# Schematic_V1.net
KiCad netlist of a schematic drawn in EAGLE
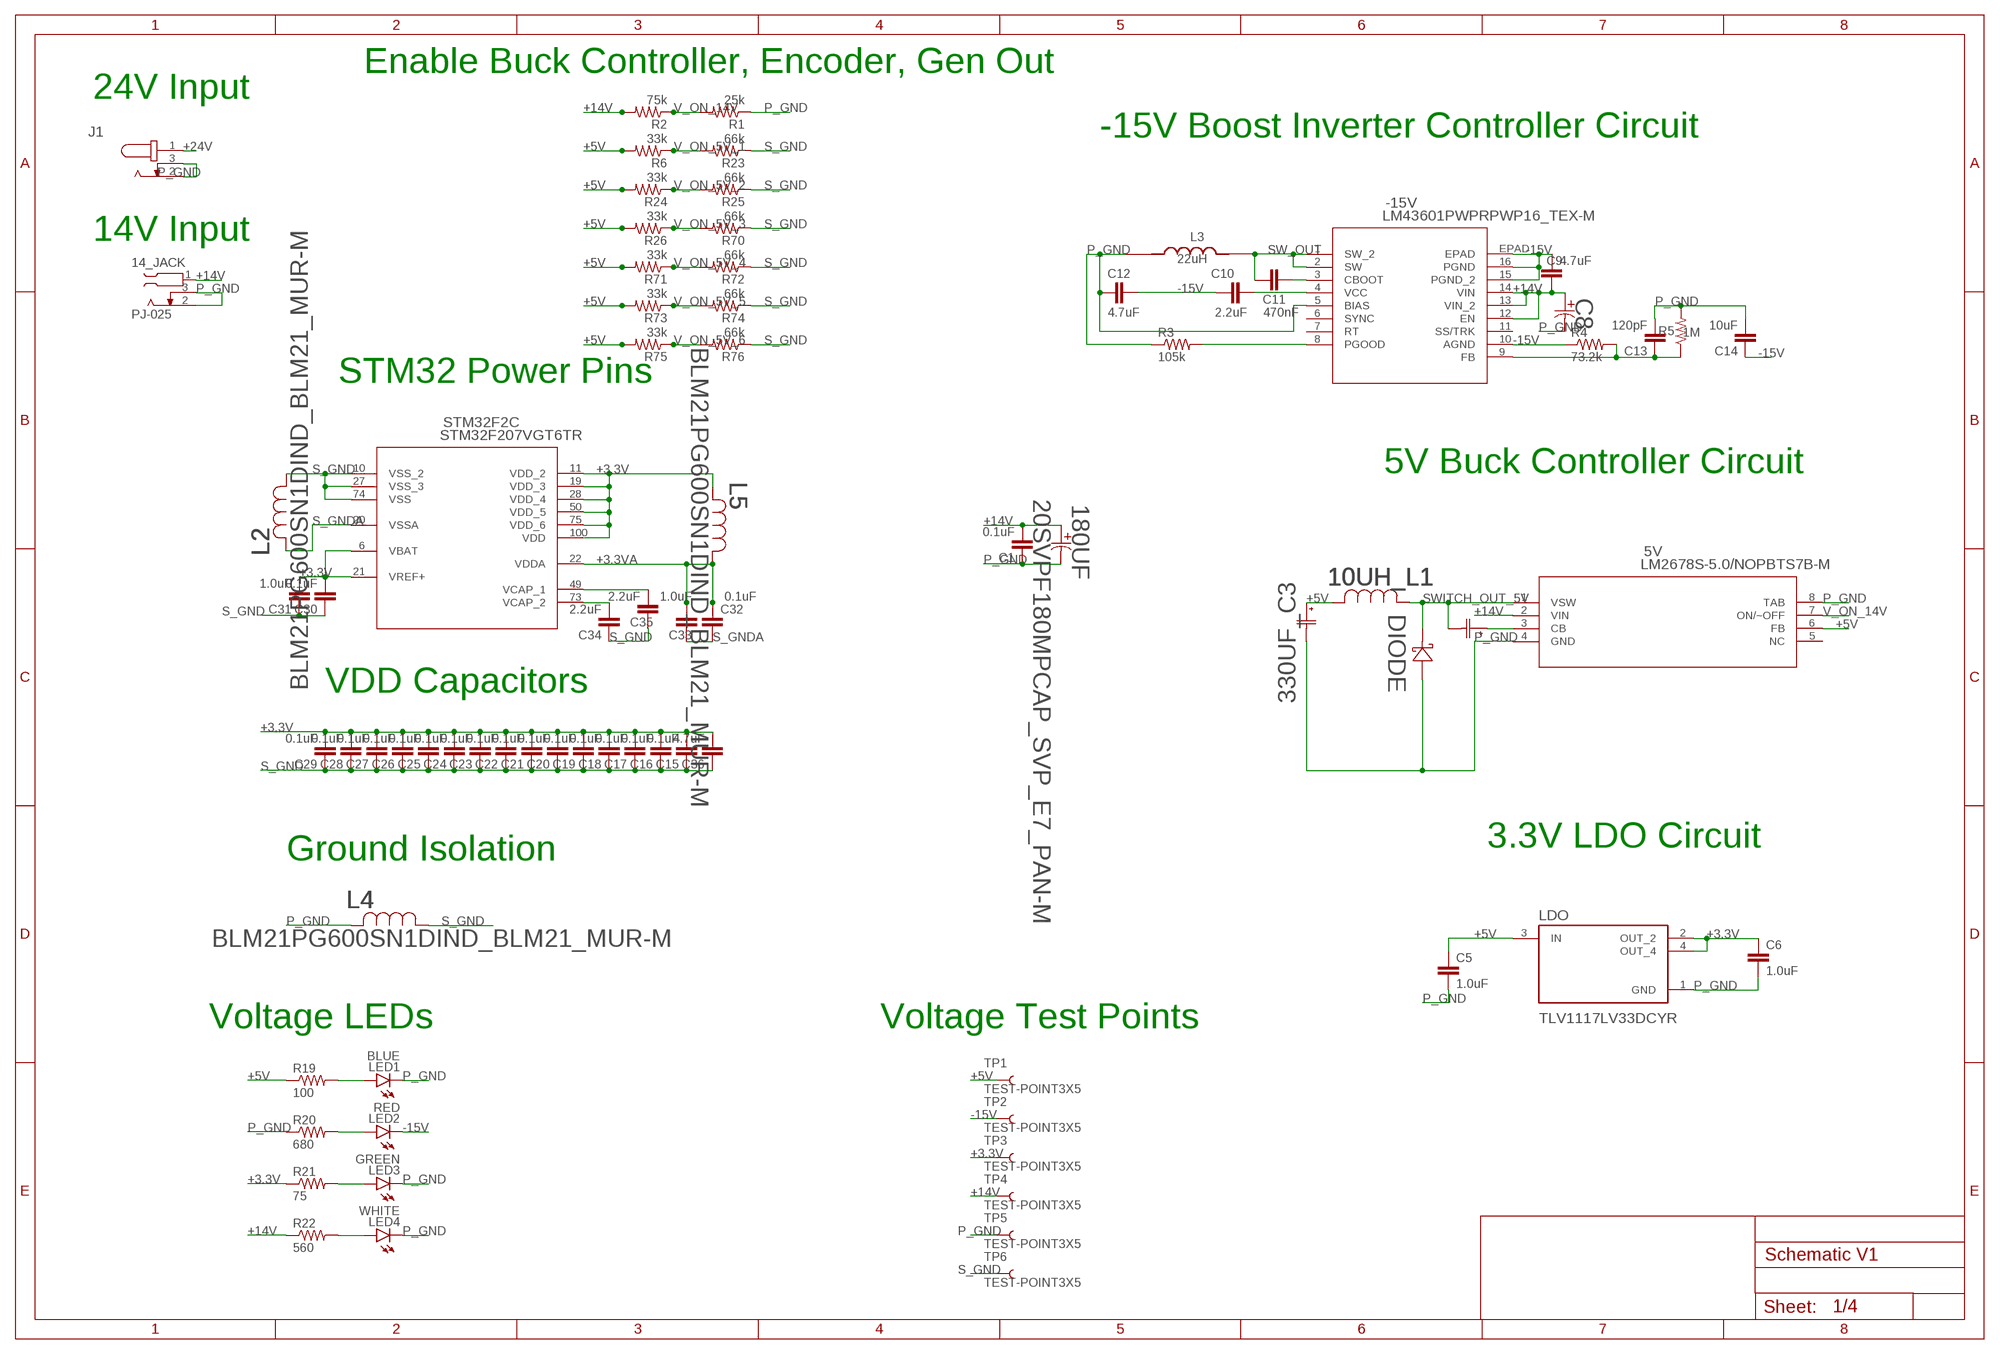
[diagram p0: schematic, sheet 1]
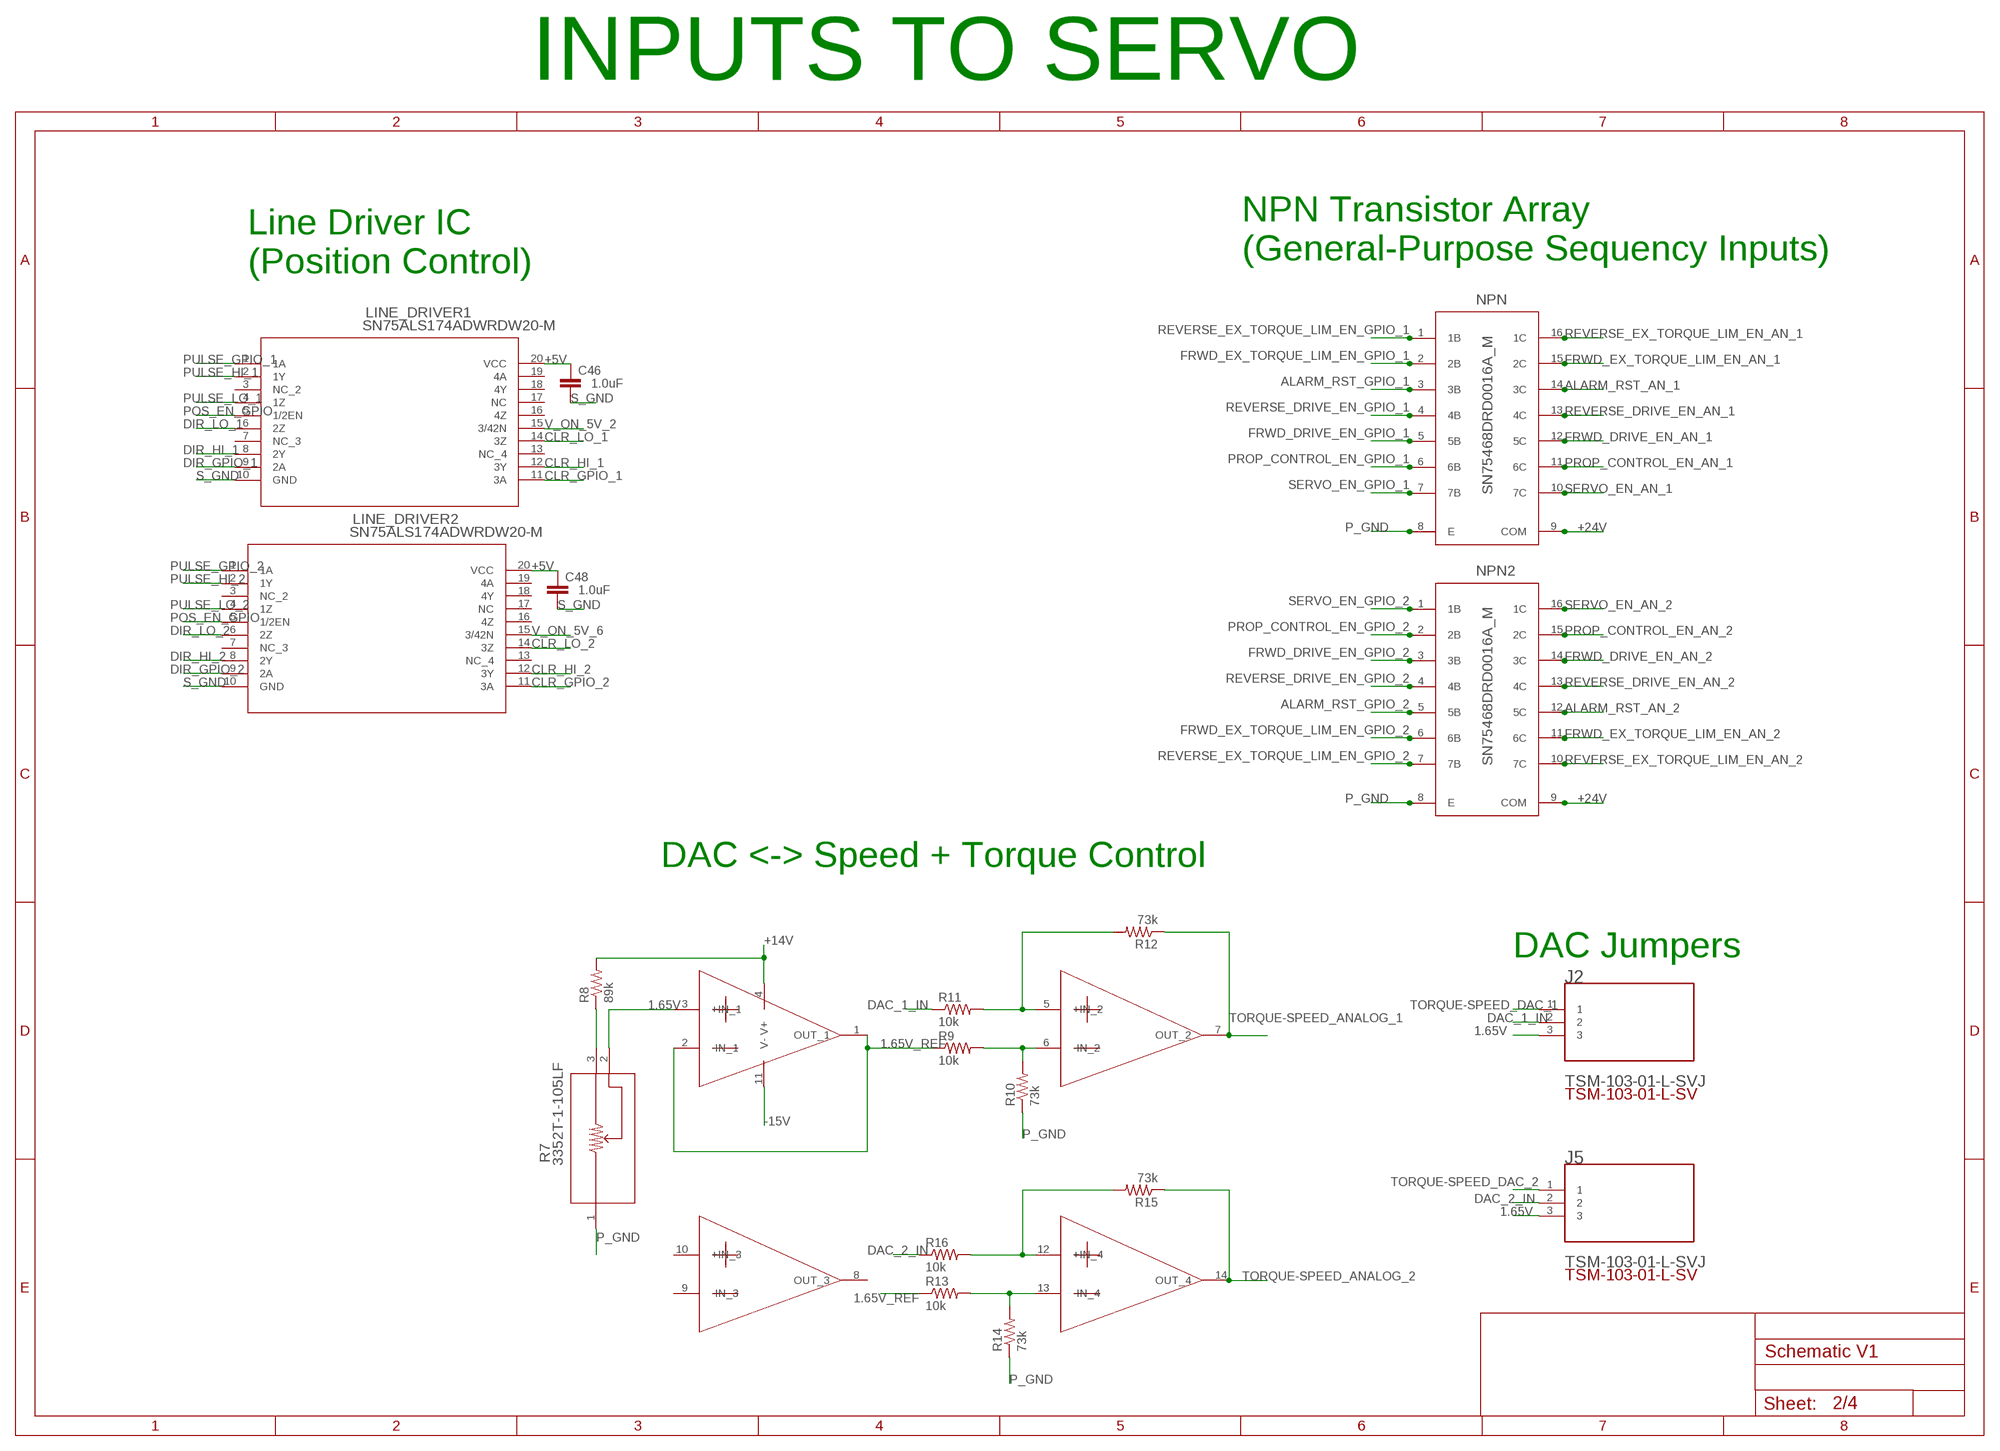
[diagram p1: schematic, sheet 2]
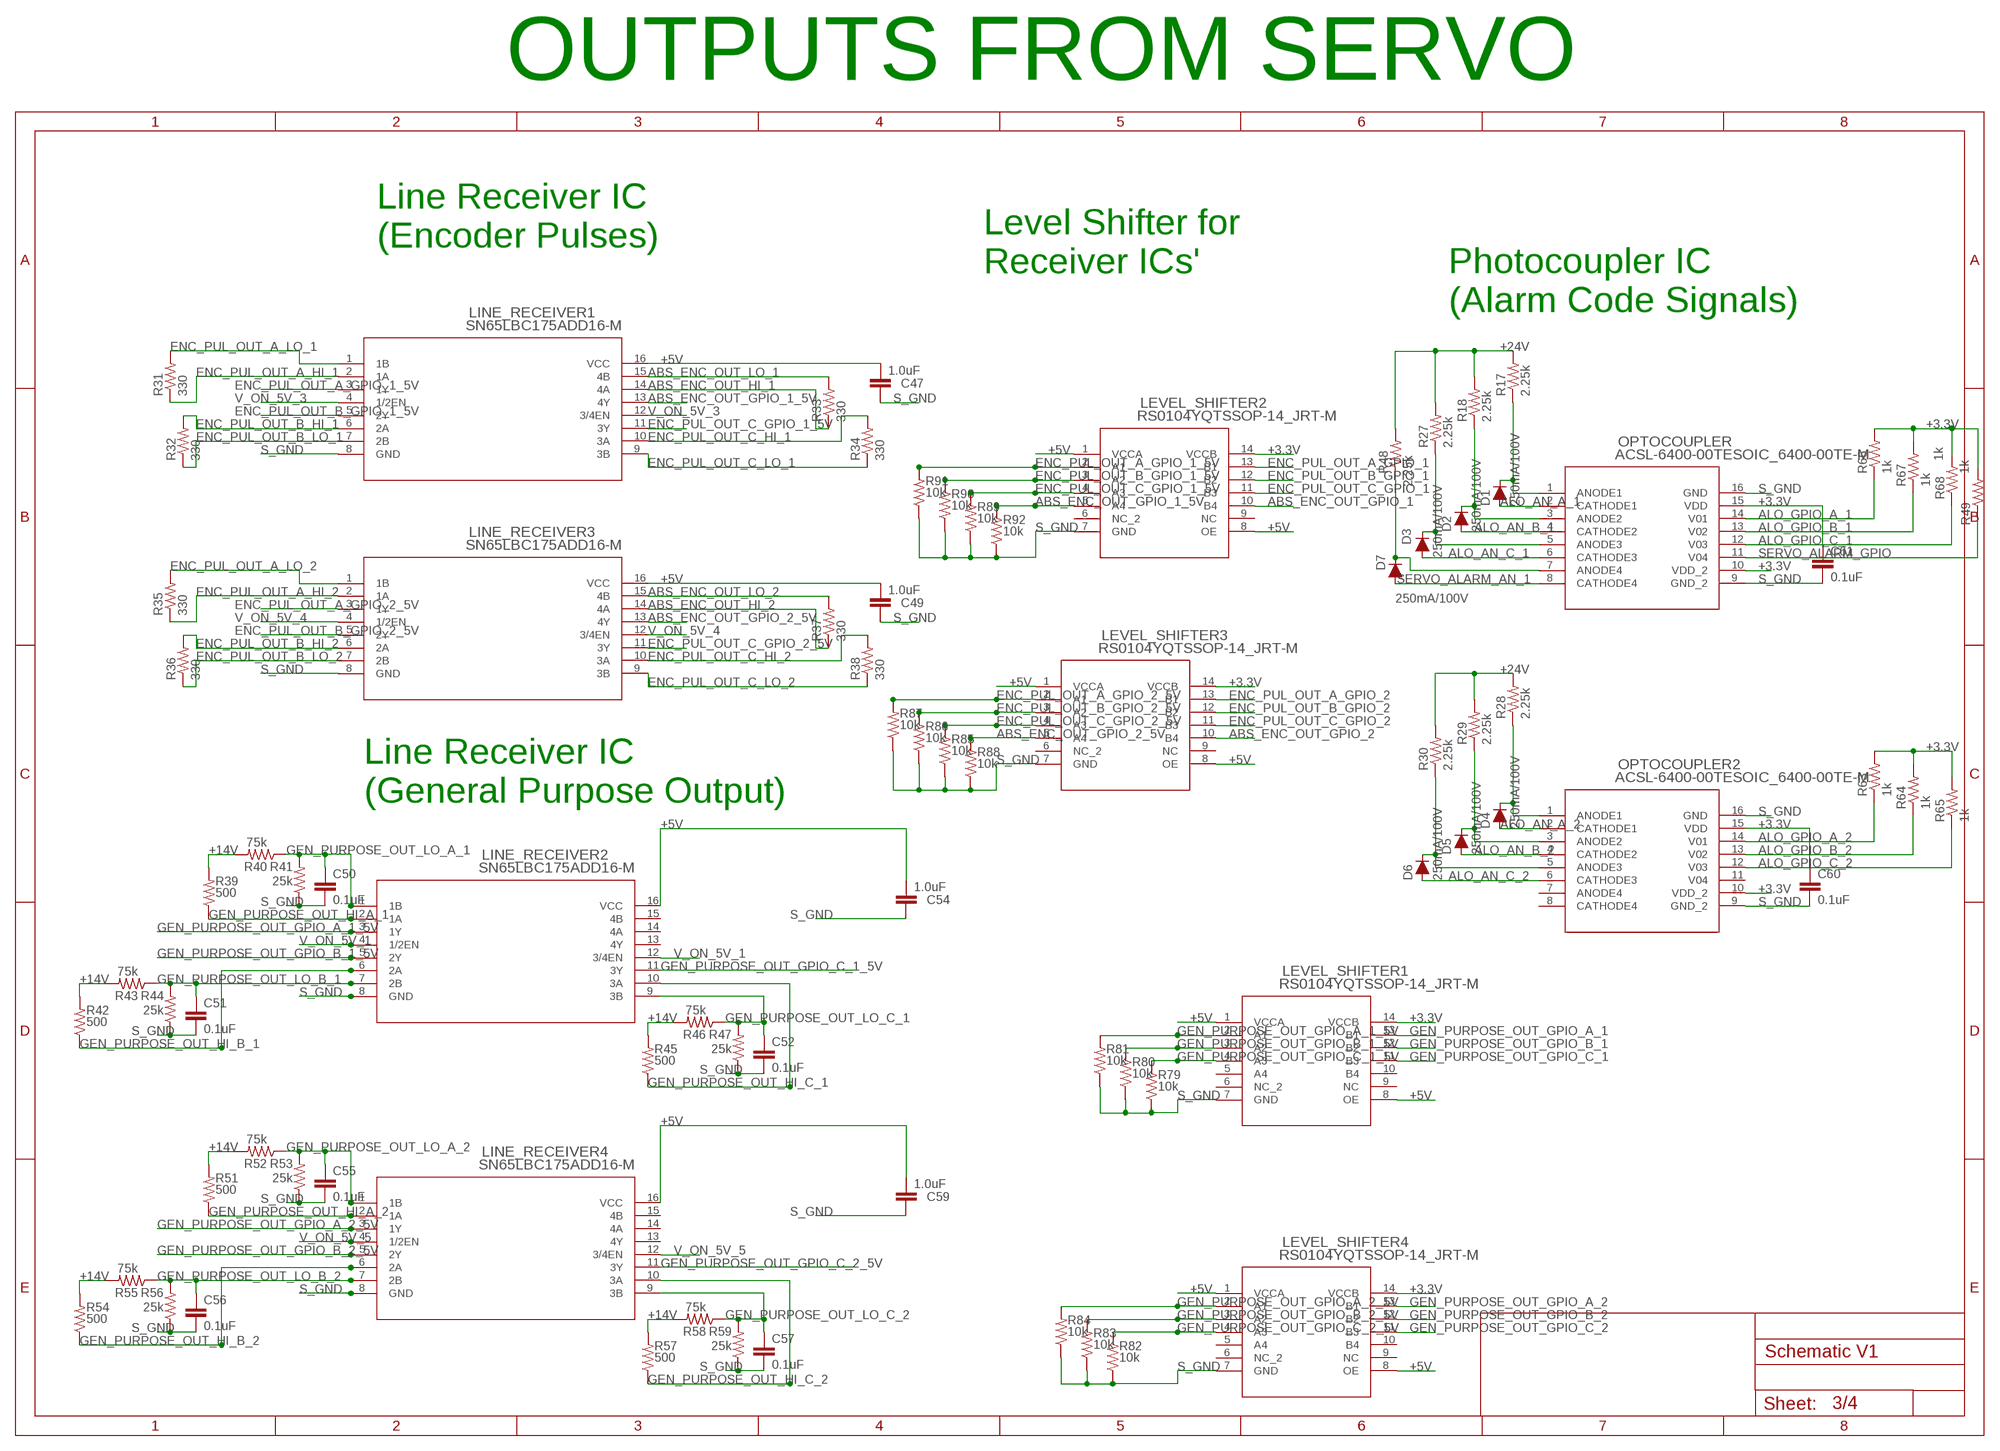
[diagram p2: schematic, sheet 3]
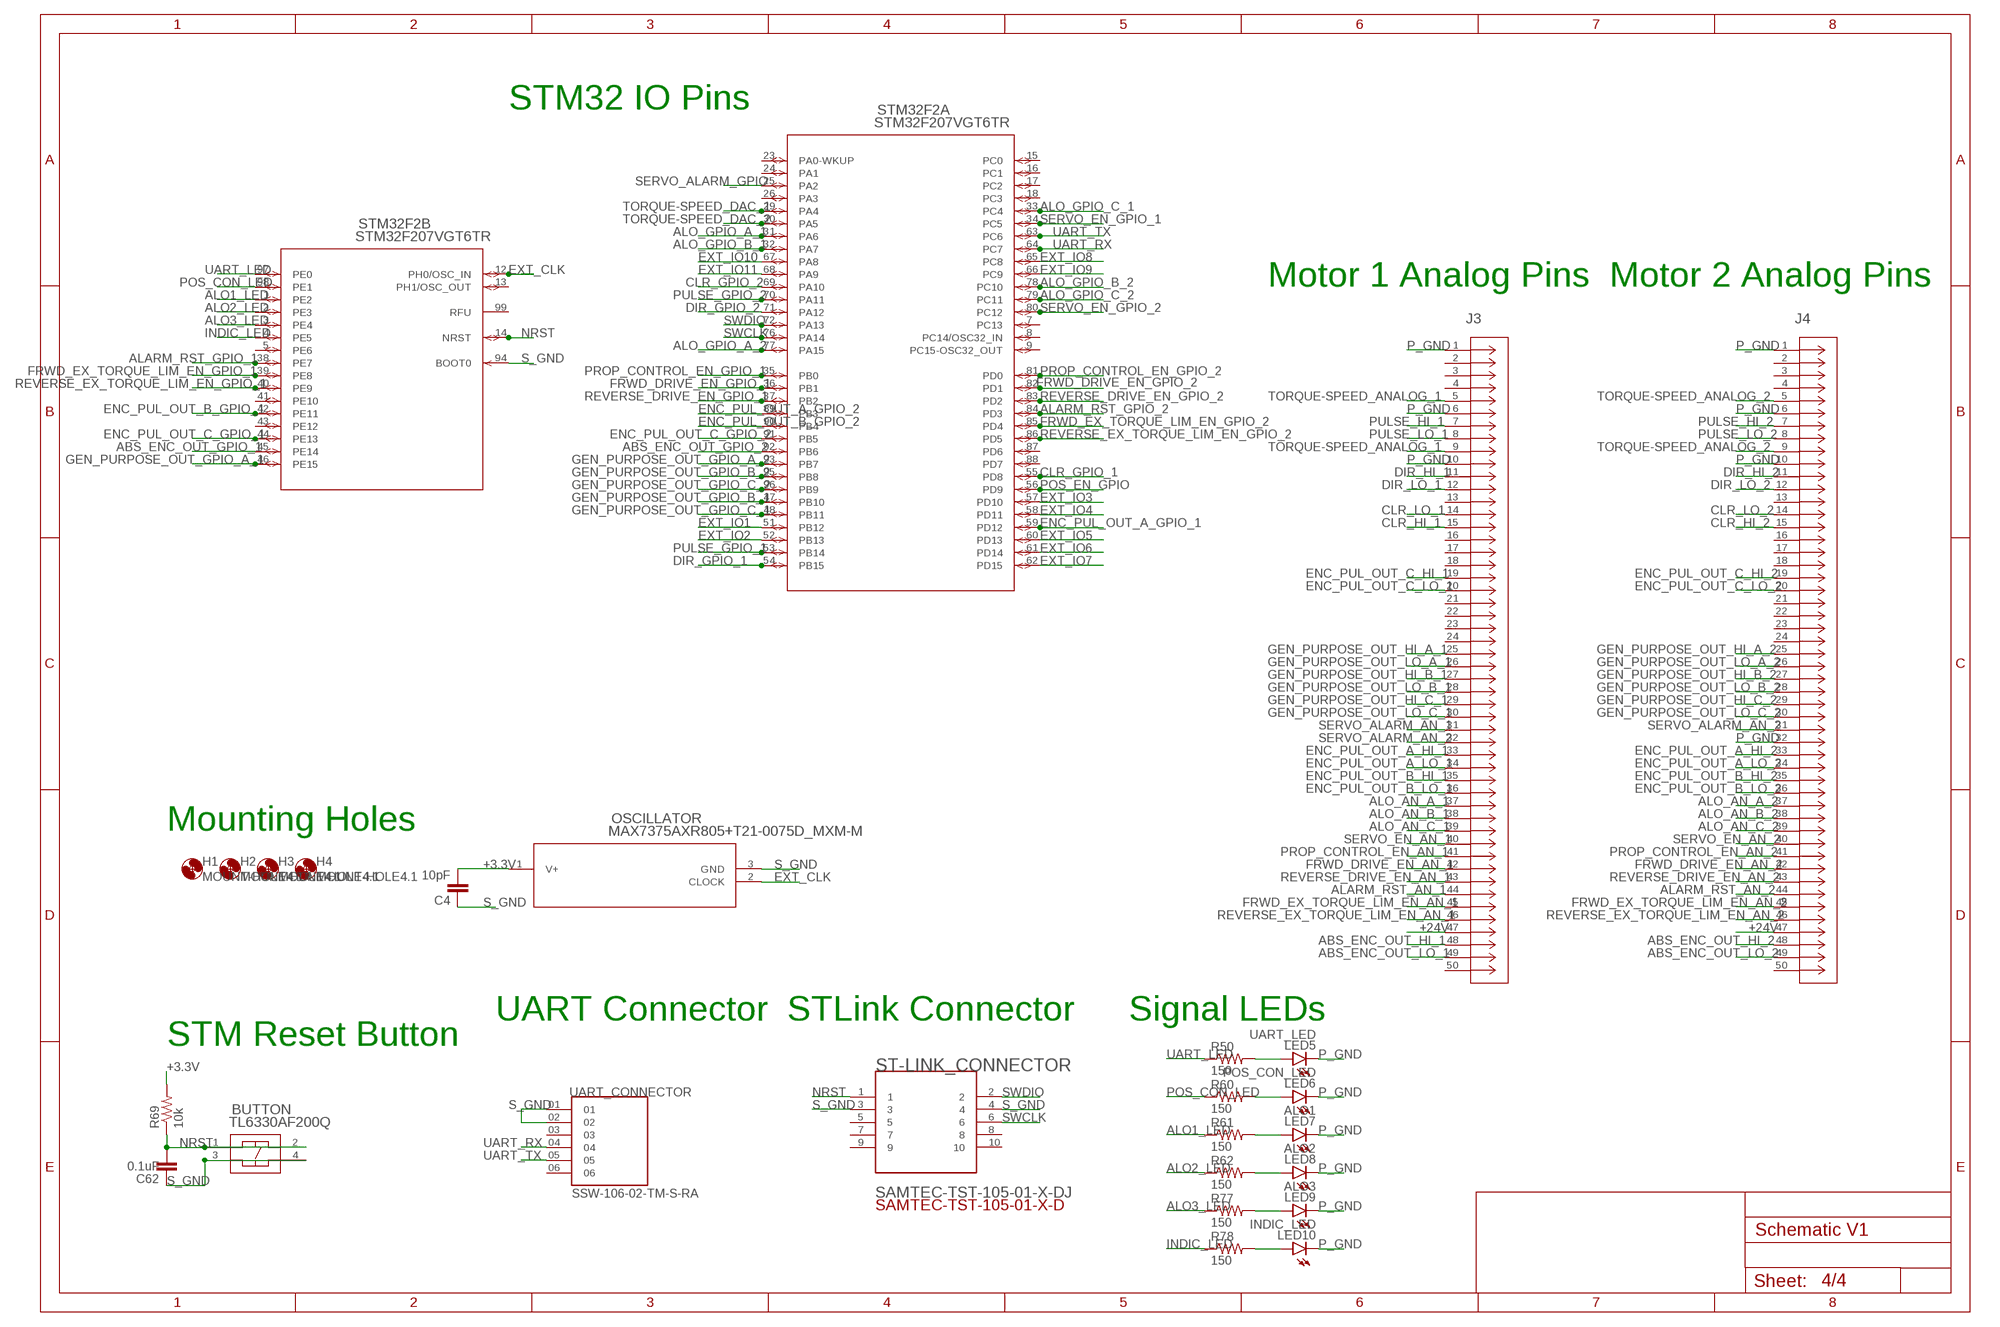
[diagram p3: schematic, sheet 4]

(export (version "E")
  (design (tool "Eeschema 10.0.6"))
  (components
    (comp (ref "BUTTON")
      (value "TL6330AF200Q")
      (footprint "eagle-import:TL6330_EWI")
      (fields (field (name "COPYRIGHT") "Copyright (C) 2024 Ultra Librarian. All rights reserved."))
      (libsource (lib "eagle-import") (part "TL6330AF200Q"))
    )
    (comp (ref "C4")
      (value "10pF")
      (footprint "eagle-import:0805")
      (libsource (lib "eagle-import") (part "10UF-0805-25V-10%"))
    )
    (comp (ref "C62")
      (value "0.1uF")
      (footprint "eagle-import:0805")
      (libsource (lib "eagle-import") (part "1.0UF-0805-25V-10%"))
    )
    (comp (ref "H1")
      (value "MOUNT-HOLE4.1")
      (footprint "eagle-import:4,1")
      (libsource (lib "eagle-import") (part "MOUNT-HOLE4.1"))
    )
    (comp (ref "H2")
      (value "MOUNT-HOLE4.1")
      (footprint "eagle-import:4,1")
      (libsource (lib "eagle-import") (part "MOUNT-HOLE4.1"))
    )
    (comp (ref "H3")
      (value "MOUNT-HOLE4.1")
      (footprint "eagle-import:4,1")
      (libsource (lib "eagle-import") (part "MOUNT-HOLE4.1"))
    )
    (comp (ref "H4")
      (value "MOUNT-HOLE4.1")
      (footprint "eagle-import:4,1")
      (libsource (lib "eagle-import") (part "MOUNT-HOLE4.1"))
    )
    (comp (ref "J3")
      (value "DD50P564GTXLF")
      (footprint "eagle-import:CONN_DD50P564GTXLF_AMP")
      (fields (field (name "COPYRIGHT") "Copyright (C) 2024 Ultra Librarian. All rights reserved."))
      (libsource (lib "eagle-import") (part "DD50P564GTXLF"))
    )
    (comp (ref "J4")
      (value "DD50P564GTXLF")
      (footprint "eagle-import:CONN_DD50P564GTXLF_AMP")
      (fields (field (name "COPYRIGHT") "Copyright (C) 2024 Ultra Librarian. All rights reserved."))
      (libsource (lib "eagle-import") (part "DD50P564GTXLF"))
    )
    (comp (ref "LED5")
      (value "UART_LED")
      (footprint "eagle-import:CHIPLED_0805")
      (libsource (lib "eagle-import") (part "LEDCHIPLED_0805"))
    )
    (comp (ref "LED6")
      (value "POS_CON_LED")
      (footprint "eagle-import:CHIPLED_0805")
      (libsource (lib "eagle-import") (part "LEDCHIPLED_0805"))
    )
    (comp (ref "LED7")
      (value "ALO1")
      (footprint "eagle-import:CHIPLED_0805")
      (libsource (lib "eagle-import") (part "LEDCHIPLED_0805"))
    )
    (comp (ref "LED8")
      (value "ALO2")
      (footprint "eagle-import:CHIPLED_0805")
      (libsource (lib "eagle-import") (part "LEDCHIPLED_0805"))
    )
    (comp (ref "LED9")
      (value "ALO3")
      (footprint "eagle-import:CHIPLED_0805")
      (libsource (lib "eagle-import") (part "LEDCHIPLED_0805"))
    )
    (comp (ref "LED10")
      (value "INDIC_LED")
      (footprint "eagle-import:CHIPLED_0805")
      (libsource (lib "eagle-import") (part "LEDCHIPLED_0805"))
    )
    (comp (ref "OSCILLATOR")
      (value "MAX7375AXR805+T21-0075D_MXM-M")
      (footprint "eagle-import:21-0075D_MXM-M")
      (fields
        (field (name "MANUFACTURER_PART_NUMBER") "MAX7375AXR805+T")
        (field (name "COPYRIGHT") "Copyright (C) 2024 Ultra Librarian. All rights reserved.")
      )
      (libsource (lib "eagle-import") (part "MAX7375AXR805+T21-0075D_MXM-M"))
    )
    (comp (ref "R50")
      (value "150")
      (footprint "eagle-import:R0805")
      (libsource (lib "eagle-import") (part "R-US_R0805"))
    )
    (comp (ref "R60")
      (value "150")
      (footprint "eagle-import:R0805")
      (libsource (lib "eagle-import") (part "R-US_R0805"))
    )
    (comp (ref "R61")
      (value "150")
      (footprint "eagle-import:R0805")
      (libsource (lib "eagle-import") (part "R-US_R0805"))
    )
    (comp (ref "R62")
      (value "150")
      (footprint "eagle-import:R0805")
      (libsource (lib "eagle-import") (part "R-US_R0805"))
    )
    (comp (ref "R69")
      (value "10k")
      (footprint "eagle-import:R0805")
      (libsource (lib "eagle-import") (part "R-US_R0805"))
    )
    (comp (ref "R77")
      (value "150")
      (footprint "eagle-import:R0805")
      (libsource (lib "eagle-import") (part "R-US_R0805"))
    )
    (comp (ref "R78")
      (value "150")
      (footprint "eagle-import:R0805")
      (libsource (lib "eagle-import") (part "R-US_R0805"))
    )
    (comp (ref "ST-LINK_CONNECTOR")
      (value "SAMTEC-TST-105-01-X-DJ")
      (footprint "eagle-import:SAMTEC-TST-105-01-X-D")
      (libsource (lib "eagle-import") (part "SAMTEC-TST-105-01-X-DJ"))
    )
    (comp (ref "STM32F2")
      (value "STM32F207VGT6TR")
      (footprint "eagle-import:LQFP100-14X14MM")
      (fields (field (name "COPYRIGHT") "Copyright (C) 2024 Ultra Librarian. All rights reserved."))
      (libsource (lib "eagle-import") (part "STM32F207VGT6TR"))
    )
    (comp (ref "UART_CONNECTOR")
      (value "SSW-106-02-TM-S-RA")
      (footprint "eagle-import:SAMTEC_SSW-106-02-TM-S-RA")
      (fields (field (name "MANUFACTURER") "Samtec"))
      (libsource (lib "eagle-import") (part "SSW-106-02-TM-S-RA"))
    )
    (comp (ref "C46")
      (value "1.0uF")
      (footprint "eagle-import:0805")
      (libsource (lib "eagle-import") (part "SparkFun-Capacitors_510_1.0UF-0805-25V-10%"))
    )
    (comp (ref "C48")
      (value "1.0uF")
      (footprint "eagle-import:0805")
      (libsource (lib "eagle-import") (part "SparkFun-Capacitors_510_1.0UF-0805-25V-10%"))
    )
    (comp (ref "J2")
      (value "TSM-103-01-L-SVJ")
      (footprint "eagle-import:TSM-103-01-L-SV")
      (libsource (lib "eagle-import") (part "TSM-103-01-L-SVJ"))
    )
    (comp (ref "J5")
      (value "TSM-103-01-L-SVJ")
      (footprint "eagle-import:TSM-103-01-L-SV")
      (libsource (lib "eagle-import") (part "TSM-103-01-L-SVJ"))
    )
    (comp (ref "LINE_DRIVER1")
      (value "SN75ALS174ADWRDW20-M")
      (footprint "eagle-import:DW20-M")
      (fields
        (field (name "MANUFACTURER_PART_NUMBER") "SN75ALS174ADWR")
        (field (name "COPYRIGHT") "Copyright (C) 2024 Ultra Librarian. All rights reserved.")
      )
      (libsource (lib "eagle-import") (part "SN75ALS174ADWRDW20-M"))
    )
    (comp (ref "LINE_DRIVER2")
      (value "SN75ALS174ADWRDW20-M")
      (footprint "eagle-import:DW20-M")
      (fields
        (field (name "MANUFACTURER_PART_NUMBER") "SN75ALS174ADWR")
        (field (name "COPYRIGHT") "Copyright (C) 2024 Ultra Librarian. All rights reserved.")
      )
      (libsource (lib "eagle-import") (part "SN75ALS174ADWRDW20-M"))
    )
    (comp (ref "NPN")
      (value "SN75468DRD0016A_M")
      (footprint "eagle-import:D0016A_M")
      (fields
        (field (name "MANUFACTURER_PART_NUMBER") "SN75468DR")
        (field (name "COPYRIGHT") "Copyright (C) 2024 Ultra Librarian. All rights reserved.")
      )
      (libsource (lib "eagle-import") (part "SN75468DRD0016A_M"))
    )
    (comp (ref "NPN2")
      (value "SN75468DRD0016A_M")
      (footprint "eagle-import:D0016A_M")
      (fields
        (field (name "MANUFACTURER_PART_NUMBER") "SN75468DR")
        (field (name "COPYRIGHT") "Copyright (C) 2024 Ultra Librarian. All rights reserved.")
      )
      (libsource (lib "eagle-import") (part "SN75468DRD0016A_M"))
    )
    (comp (ref "OP_AMP")
      (value "OPA4205APWRTSSOP14_PW_R-PDSO-G14_TEX-M")
      (footprint "eagle-import:TSSOP14_PW_R-PDSO-G14_TEX-M")
      (fields
        (field (name "MANUFACTURER_PART_NUMBER") "OPA4205APWR")
        (field (name "COPYRIGHT") "Copyright (C) 2024 Ultra Librarian. All rights reserved.")
      )
      (libsource (lib "eagle-import") (part "OPA4205APWRTSSOP14_PW_R-PDSO-G14_TEX-M"))
    )
    (comp (ref "R7")
      (value "3352T-1-105LF")
      (footprint "eagle-import:3352T_BRN")
      (fields (field (name "COPYRIGHT") "Copyright (C) 2024 Ultra Librarian. All rights reserved."))
      (libsource (lib "eagle-import") (part "3352T-1-105LF"))
    )
    (comp (ref "R8")
      (value "89k")
      (footprint "eagle-import:R0805")
      (libsource (lib "eagle-import") (part "R-US_R0805"))
    )
    (comp (ref "R9")
      (value "10k")
      (footprint "eagle-import:R0805")
      (libsource (lib "eagle-import") (part "R-US_R0805"))
    )
    (comp (ref "R10")
      (value "73k")
      (footprint "eagle-import:R0805")
      (libsource (lib "eagle-import") (part "R-US_R0805"))
    )
    (comp (ref "R11")
      (value "10k")
      (footprint "eagle-import:R0805")
      (libsource (lib "eagle-import") (part "R-US_R0805"))
    )
    (comp (ref "R12")
      (value "73k")
      (footprint "eagle-import:R0805")
      (libsource (lib "eagle-import") (part "R-US_R0805"))
    )
    (comp (ref "R13")
      (value "10k")
      (footprint "eagle-import:R0805")
      (libsource (lib "eagle-import") (part "R-US_R0805"))
    )
    (comp (ref "R14")
      (value "73k")
      (footprint "eagle-import:R0805")
      (libsource (lib "eagle-import") (part "R-US_R0805"))
    )
    (comp (ref "R15")
      (value "73k")
      (footprint "eagle-import:R0805")
      (libsource (lib "eagle-import") (part "R-US_R0805"))
    )
    (comp (ref "R16")
      (value "10k")
      (footprint "eagle-import:R0805")
      (libsource (lib "eagle-import") (part "R-US_R0805"))
    )
    (comp (ref "-15V")
      (value "LM43601PWPRPWP16_TEX-M")
      (footprint "eagle-import:PWP16_TEX-M")
      (fields
        (field (name "MANUFACTURER_PART_NUMBER") "LM43601PWPR")
        (field (name "COPYRIGHT") "Copyright (C) 2024 Ultra Librarian. All rights reserved.")
      )
      (libsource (lib "eagle-import") (part "LM43601PWPRPWP16_TEX-M"))
    )
    (comp (ref "0.01UF_C7")
      (value "GRM2195C1H103JA01DG-21_MUR-M")
      (footprint "eagle-import:G-21_MUR-M")
      (fields
        (field (name "MANUFACTURER_PART_NUMBER") "GRM2195C1H103JA01D")
        (field (name "COPYRIGHT") "Copyright (C) 2024 Ultra Librarian. All rights reserved.")
      )
      (libsource (lib "eagle-import") (part "GRM2195C1H103JA01DG-21_MUR-M"))
    )
    (comp (ref "5V")
      (value "LM2678S-5.0/NOPBTS7B-M")
      (footprint "eagle-import:TS7B-M")
      (fields
        (field (name "MANUFACTURER_PART_NUMBER") "LM2678S-5.0/NOPB")
        (field (name "COPYRIGHT") "Copyright (C) 2024 Ultra Librarian. All rights reserved.")
      )
      (libsource (lib "eagle-import") (part "LM2678S-5.0/NOPBTS7B-M"))
    )
    (comp (ref "10UH_L1")
      (value "SRP1270-100MIND_BOURNS_SRP1270-M")
      (footprint "eagle-import:IND_BOURNS_SRP1270-M")
      (fields
        (field (name "MANUFACTURER_PART_NUMBER") "SRP1270-100M")
        (field (name "COPYRIGHT") "Copyright (C) 2024 Ultra Librarian. All rights reserved.")
      )
      (libsource (lib "eagle-import") (part "SRP1270-100MIND_BOURNS_SRP1270-M"))
    )
    (comp (ref "14_JACK")
      (value "PJ-025")
      (footprint "eagle-import:CUI_PJ-025")
      (fields (field (name "MANUFACTURER") "CUI INC"))
      (libsource (lib "eagle-import") (part "PJ-025"))
    )
    (comp (ref "180UF")
      (value "20SVPF180MPCAP_SVP_E7_PAN-M")
      (footprint "eagle-import:PCAP_SVP_E7_PAN-M")
      (fields
        (field (name "MANUFACTURER_PART_NUMBER") "20SVPF180M")
        (field (name "COPYRIGHT") "Copyright (C) 2024 Ultra Librarian. All rights reserved.")
      )
      (libsource (lib "eagle-import") (part "20SVPF180MPCAP_SVP_E7_PAN-M"))
    )
    (comp (ref "330UF_C3")
      (value "10SVPC330MCAP_SVPC_E7_PAN-M")
      (footprint "eagle-import:CAP_SVPC_E7_PAN-M")
      (fields
        (field (name "MANUFACTURER_PART_NUMBER") "10SVPC330M")
        (field (name "COPYRIGHT") "Copyright (C) 2024 Ultra Librarian. All rights reserved.")
      )
      (libsource (lib "eagle-import") (part "10SVPC330MCAP_SVPC_E7_PAN-M"))
    )
    (comp (ref "C1")
      (value "0.1uF")
      (footprint "eagle-import:0805")
      (libsource (lib "eagle-import") (part "1.0UF-0805-25V-(+80/-20%)"))
    )
    (comp (ref "C5")
      (value "1.0uF")
      (footprint "eagle-import:0805")
      (libsource (lib "eagle-import") (part "SparkFun-Capacitors_510_1.0UF-0805-25V-(+80/-20%)"))
    )
    (comp (ref "C6")
      (value "1.0uF")
      (footprint "eagle-import:0805")
      (libsource (lib "eagle-import") (part "SparkFun-Capacitors_510_1.0UF-0805-25V-(+80/-20%)"))
    )
    (comp (ref "C8")
      (value "68uF")
      (footprint "eagle-import:PCAP_6.3X7.7-ELECT_NCA-M")
      (fields
        (field (name "MANUFACTURER_PART_NUMBER") "UWD1V680MCL1GS")
        (field (name "COPYRIGHT") "Copyright (C) 2024 Ultra Librarian. All rights reserved.")
      )
      (libsource (lib "eagle-import") (part "UWD1V680MCL1GSPCAP_6.3X7.7-ELECT_NCA-M"))
    )
    (comp (ref "C9")
      (value "4.7uF")
      (footprint "eagle-import:0805")
      (libsource (lib "eagle-import") (part "4.7UF-0805-50V-(10%)"))
    )
    (comp (ref "C10")
      (value "2.2uF")
      (footprint "eagle-import:0805")
      (libsource (lib "eagle-import") (part "2.2UF-0805-25V-(+80/-20%)"))
    )
    (comp (ref "C11")
      (value "470nF")
      (footprint "eagle-import:0805")
      (libsource (lib "eagle-import") (part "470NF-0805-100V-10%-X7S"))
    )
    (comp (ref "C12")
      (value "4.7uF")
      (footprint "eagle-import:0805")
      (libsource (lib "eagle-import") (part "4.7UF-0805-50V-(10%)"))
    )
    (comp (ref "C13")
      (value "120pF")
      (footprint "eagle-import:0805")
      (libsource (lib "eagle-import") (part "4.7UF-0805-50V-(10%)"))
    )
    (comp (ref "C14")
      (value "10uF")
      (footprint "eagle-import:0805")
      (libsource (lib "eagle-import") (part "4.7UF-0805-50V-(10%)"))
    )
    (comp (ref "C15")
      (value "0.1uF")
      (footprint "eagle-import:0805")
      (libsource (lib "eagle-import") (part "SparkFun-Capacitors_510_1.0UF-0805-25V-10%"))
    )
    (comp (ref "C16")
      (value "0.1uF")
      (footprint "eagle-import:0805")
      (libsource (lib "eagle-import") (part "SparkFun-Capacitors_510_1.0UF-0805-25V-10%"))
    )
    (comp (ref "C17")
      (value "0.1uF")
      (footprint "eagle-import:0805")
      (libsource (lib "eagle-import") (part "SparkFun-Capacitors_510_1.0UF-0805-25V-10%"))
    )
    (comp (ref "C18")
      (value "0.1uF")
      (footprint "eagle-import:0805")
      (libsource (lib "eagle-import") (part "SparkFun-Capacitors_510_1.0UF-0805-25V-10%"))
    )
    (comp (ref "C19")
      (value "0.1uF")
      (footprint "eagle-import:0805")
      (libsource (lib "eagle-import") (part "SparkFun-Capacitors_510_1.0UF-0805-25V-10%"))
    )
    (comp (ref "C20")
      (value "0.1uF")
      (footprint "eagle-import:0805")
      (libsource (lib "eagle-import") (part "SparkFun-Capacitors_510_1.0UF-0805-25V-10%"))
    )
    (comp (ref "C21")
      (value "0.1uF")
      (footprint "eagle-import:0805")
      (libsource (lib "eagle-import") (part "SparkFun-Capacitors_510_1.0UF-0805-25V-10%"))
    )
    (comp (ref "C22")
      (value "0.1uF")
      (footprint "eagle-import:0805")
      (libsource (lib "eagle-import") (part "SparkFun-Capacitors_510_1.0UF-0805-25V-10%"))
    )
    (comp (ref "C23")
      (value "0.1uF")
      (footprint "eagle-import:0805")
      (libsource (lib "eagle-import") (part "SparkFun-Capacitors_510_1.0UF-0805-25V-10%"))
    )
    (comp (ref "C24")
      (value "0.1uF")
      (footprint "eagle-import:0805")
      (libsource (lib "eagle-import") (part "SparkFun-Capacitors_510_1.0UF-0805-25V-10%"))
    )
    (comp (ref "C25")
      (value "0.1uF")
      (footprint "eagle-import:0805")
      (libsource (lib "eagle-import") (part "SparkFun-Capacitors_510_1.0UF-0805-25V-10%"))
    )
    (comp (ref "C26")
      (value "0.1uF")
      (footprint "eagle-import:0805")
      (libsource (lib "eagle-import") (part "SparkFun-Capacitors_510_1.0UF-0805-25V-10%"))
    )
    (comp (ref "C27")
      (value "0.1uF")
      (footprint "eagle-import:0805")
      (libsource (lib "eagle-import") (part "SparkFun-Capacitors_510_1.0UF-0805-25V-10%"))
    )
    (comp (ref "C28")
      (value "0.1uF")
      (footprint "eagle-import:0805")
      (libsource (lib "eagle-import") (part "SparkFun-Capacitors_510_1.0UF-0805-25V-10%"))
    )
    (comp (ref "C29")
      (value "0.1uF")
      (footprint "eagle-import:0805")
      (libsource (lib "eagle-import") (part "SparkFun-Capacitors_510_1.0UF-0805-25V-10%"))
    )
    (comp (ref "C30")
      (value "0.1uF")
      (footprint "eagle-import:0805")
      (libsource (lib "eagle-import") (part "SparkFun-Capacitors_510_1.0UF-0805-25V-10%"))
    )
    (comp (ref "C31")
      (value "1.0uF")
      (footprint "eagle-import:0805")
      (libsource (lib "eagle-import") (part "SparkFun-Capacitors_510_1.0UF-0805-25V-10%"))
    )
    (comp (ref "C32")
      (value "0.1uF")
      (footprint "eagle-import:0805")
      (libsource (lib "eagle-import") (part "SparkFun-Capacitors_510_1.0UF-0805-25V-10%"))
    )
    (comp (ref "C33")
      (value "1.0uF")
      (footprint "eagle-import:0805")
      (libsource (lib "eagle-import") (part "SparkFun-Capacitors_510_1.0UF-0805-25V-10%"))
    )
    (comp (ref "C34")
      (value "2.2uF")
      (footprint "eagle-import:0805")
      (libsource (lib "eagle-import") (part "SparkFun-Capacitors_510_2.2UF-0805-25V-(+80/-20%)"))
    )
    (comp (ref "C35")
      (value "2.2uF")
      (footprint "eagle-import:0805")
      (libsource (lib "eagle-import") (part "SparkFun-Capacitors_510_2.2UF-0805-25V-(+80/-20%)"))
    )
    (comp (ref "C36")
      (value "4.7uF")
      (footprint "eagle-import:0805")
      (libsource (lib "eagle-import") (part "SparkFun-Capacitors_510_2.2UF-0805-25V-(+80/-20%)"))
    )
    (comp (ref "DIODE")
      (value "CDBC520-GCDBC-G-M")
      (footprint "eagle-import:CDBC-G-M")
      (fields
        (field (name "MANUFACTURER_PART_NUMBER") "CDBC520-G")
        (field (name "COPYRIGHT") "Copyright (C) 2024 Ultra Librarian. All rights reserved.")
      )
      (libsource (lib "eagle-import") (part "CDBC520-GCDBC-G-M"))
    )
    (comp (ref "J1")
      (value "PJ-202AH")
      (footprint "eagle-import:CUI_PJ-202AH")
      (fields (field (name "MANUFACTURER") "CUI INC"))
      (libsource (lib "eagle-import") (part "PJ-202AH"))
    )
    (comp (ref "L2")
      (value "BLM21PG600SN1DIND_BLM21_MUR-M")
      (footprint "eagle-import:IND_BLM21_MUR-M")
      (fields
        (field (name "MANUFACTURER_PART_NUMBER") "BLM21PG600SN1D")
        (field (name "COPYRIGHT") "Copyright (C) 2024 Ultra Librarian. All rights reserved.")
      )
      (libsource (lib "eagle-import") (part "BLM21PG600SN1DIND_BLM21_MUR-M"))
    )
    (comp (ref "L3")
      (value "22uH")
      (footprint "eagle-import:IND_VLS201610CX-220M-1")
      (fields (field (name "MANUFACTURER") "TDK"))
      (libsource (lib "eagle-import") (part "VLS201610CX-220M-1"))
    )
    (comp (ref "L4")
      (value "BLM21PG600SN1DIND_BLM21_MUR-M")
      (footprint "eagle-import:IND_BLM21_MUR-M")
      (fields
        (field (name "MANUFACTURER_PART_NUMBER") "BLM21PG600SN1D")
        (field (name "COPYRIGHT") "Copyright (C) 2024 Ultra Librarian. All rights reserved.")
      )
      (libsource (lib "eagle-import") (part "BLM21PG600SN1DIND_BLM21_MUR-M"))
    )
    (comp (ref "L5")
      (value "BLM21PG600SN1DIND_BLM21_MUR-M")
      (footprint "eagle-import:IND_BLM21_MUR-M")
      (fields
        (field (name "MANUFACTURER_PART_NUMBER") "BLM21PG600SN1D")
        (field (name "COPYRIGHT") "Copyright (C) 2024 Ultra Librarian. All rights reserved.")
      )
      (libsource (lib "eagle-import") (part "BLM21PG600SN1DIND_BLM21_MUR-M"))
    )
    (comp (ref "LDO")
      (value "TLV1117LV33DCYR")
      (footprint "eagle-import:VREG_TLV1117LV33DCYR")
      (fields (field (name "MANUFACTURER") "Texas Instruments"))
      (libsource (lib "eagle-import") (part "TLV1117LV33DCYR"))
    )
    (comp (ref "LED1")
      (value "BLUE")
      (footprint "eagle-import:CHIPLED_0805")
      (libsource (lib "eagle-import") (part "LEDCHIPLED_0805"))
    )
    (comp (ref "LED2")
      (value "RED")
      (footprint "eagle-import:CHIPLED_0805")
      (libsource (lib "eagle-import") (part "LEDCHIPLED_0805"))
    )
    (comp (ref "LED3")
      (value "GREEN")
      (footprint "eagle-import:CHIPLED_0805")
      (libsource (lib "eagle-import") (part "LEDCHIPLED_0805"))
    )
    (comp (ref "LED4")
      (value "WHITE")
      (footprint "eagle-import:CHIPLED_0805")
      (libsource (lib "eagle-import") (part "LEDCHIPLED_0805"))
    )
    (comp (ref "R1")
      (value "25k")
      (footprint "eagle-import:R0805")
      (libsource (lib "eagle-import") (part "R-US_R0805"))
    )
    (comp (ref "R2")
      (value "75k")
      (footprint "eagle-import:R0805")
      (libsource (lib "eagle-import") (part "R-US_R0805"))
    )
    (comp (ref "R3")
      (value "105k")
      (footprint "eagle-import:R0805")
      (libsource (lib "eagle-import") (part "R-US_R0805"))
    )
    (comp (ref "R4")
      (value "73.2k")
      (footprint "eagle-import:R0805")
      (libsource (lib "eagle-import") (part "R-US_R0805"))
    )
    (comp (ref "R5")
      (value "1M")
      (footprint "eagle-import:R0805")
      (libsource (lib "eagle-import") (part "R-US_R0805"))
    )
    (comp (ref "R6")
      (value "33k")
      (footprint "eagle-import:R0805")
      (libsource (lib "eagle-import") (part "R-US_R0805"))
    )
    (comp (ref "R19")
      (value "100")
      (footprint "eagle-import:R0805")
      (libsource (lib "eagle-import") (part "R-US_R0805"))
    )
    (comp (ref "R20")
      (value "680")
      (footprint "eagle-import:R0805")
      (libsource (lib "eagle-import") (part "R-US_R0805"))
    )
    (comp (ref "R21")
      (value "75")
      (footprint "eagle-import:R0805")
      (libsource (lib "eagle-import") (part "R-US_R0805"))
    )
    (comp (ref "R22")
      (value "560")
      (footprint "eagle-import:R0805")
      (libsource (lib "eagle-import") (part "R-US_R0805"))
    )
    (comp (ref "R23")
      (value "66k")
      (footprint "eagle-import:R0805")
      (libsource (lib "eagle-import") (part "R-US_R0805"))
    )
    (comp (ref "R24")
      (value "33k")
      (footprint "eagle-import:R0805")
      (libsource (lib "eagle-import") (part "R-US_R0805"))
    )
    (comp (ref "R25")
      (value "66k")
      (footprint "eagle-import:R0805")
      (libsource (lib "eagle-import") (part "R-US_R0805"))
    )
    (comp (ref "R26")
      (value "33k")
      (footprint "eagle-import:R0805")
      (libsource (lib "eagle-import") (part "R-US_R0805"))
    )
    (comp (ref "R70")
      (value "66k")
      (footprint "eagle-import:R0805")
      (libsource (lib "eagle-import") (part "R-US_R0805"))
    )
    (comp (ref "R71")
      (value "33k")
      (footprint "eagle-import:R0805")
      (libsource (lib "eagle-import") (part "R-US_R0805"))
    )
    (comp (ref "R72")
      (value "66k")
      (footprint "eagle-import:R0805")
      (libsource (lib "eagle-import") (part "R-US_R0805"))
    )
    (comp (ref "R73")
      (value "33k")
      (footprint "eagle-import:R0805")
      (libsource (lib "eagle-import") (part "R-US_R0805"))
    )
    (comp (ref "R74")
      (value "66k")
      (footprint "eagle-import:R0805")
      (libsource (lib "eagle-import") (part "R-US_R0805"))
    )
    (comp (ref "R75")
      (value "33k")
      (footprint "eagle-import:R0805")
      (libsource (lib "eagle-import") (part "R-US_R0805"))
    )
    (comp (ref "R76")
      (value "66k")
      (footprint "eagle-import:R0805")
      (libsource (lib "eagle-import") (part "R-US_R0805"))
    )
    (comp (ref "TP1")
      (value "TEST-POINT3X5")
      (footprint "eagle-import:PAD.03X.05")
      (libsource (lib "eagle-import") (part "TEST-POINT3X5"))
    )
    (comp (ref "TP2")
      (value "TEST-POINT3X5")
      (footprint "eagle-import:PAD.03X.05")
      (libsource (lib "eagle-import") (part "TEST-POINT3X5"))
    )
    (comp (ref "TP3")
      (value "TEST-POINT3X5")
      (footprint "eagle-import:PAD.03X.05")
      (libsource (lib "eagle-import") (part "TEST-POINT3X5"))
    )
    (comp (ref "TP4")
      (value "TEST-POINT3X5")
      (footprint "eagle-import:PAD.03X.05")
      (libsource (lib "eagle-import") (part "TEST-POINT3X5"))
    )
    (comp (ref "TP5")
      (value "TEST-POINT3X5")
      (footprint "eagle-import:PAD.03X.05")
      (libsource (lib "eagle-import") (part "TEST-POINT3X5"))
    )
    (comp (ref "TP6")
      (value "TEST-POINT3X5")
      (footprint "eagle-import:PAD.03X.05")
      (libsource (lib "eagle-import") (part "TEST-POINT3X5"))
    )
    (comp (ref "C47")
      (value "1.0uF")
      (footprint "eagle-import:0805")
      (libsource (lib "eagle-import") (part "SparkFun-Capacitors_510_1.0UF-0805-25V-10%"))
    )
    (comp (ref "C49")
      (value "1.0uF")
      (footprint "eagle-import:0805")
      (libsource (lib "eagle-import") (part "SparkFun-Capacitors_510_1.0UF-0805-25V-10%"))
    )
    (comp (ref "C50")
      (value "0.1uF")
      (footprint "eagle-import:0805")
      (libsource (lib "eagle-import") (part "SparkFun-Capacitors_510_1.0UF-0805-25V-10%"))
    )
    (comp (ref "C51")
      (value "0.1uF")
      (footprint "eagle-import:0805")
      (libsource (lib "eagle-import") (part "SparkFun-Capacitors_510_1.0UF-0805-25V-10%"))
    )
    (comp (ref "C52")
      (value "0.1uF")
      (footprint "eagle-import:0805")
      (libsource (lib "eagle-import") (part "SparkFun-Capacitors_510_1.0UF-0805-25V-10%"))
    )
    (comp (ref "C54")
      (value "1.0uF")
      (footprint "eagle-import:0805")
      (libsource (lib "eagle-import") (part "SparkFun-Capacitors_510_1.0UF-0805-25V-10%"))
    )
    (comp (ref "C55")
      (value "0.1uF")
      (footprint "eagle-import:0805")
      (libsource (lib "eagle-import") (part "SparkFun-Capacitors_510_1.0UF-0805-25V-10%"))
    )
    (comp (ref "C56")
      (value "0.1uF")
      (footprint "eagle-import:0805")
      (libsource (lib "eagle-import") (part "SparkFun-Capacitors_510_1.0UF-0805-25V-10%"))
    )
    (comp (ref "C57")
      (value "0.1uF")
      (footprint "eagle-import:0805")
      (libsource (lib "eagle-import") (part "SparkFun-Capacitors_510_1.0UF-0805-25V-10%"))
    )
    (comp (ref "C59")
      (value "1.0uF")
      (footprint "eagle-import:0805")
      (libsource (lib "eagle-import") (part "SparkFun-Capacitors_510_1.0UF-0805-25V-10%"))
    )
    (comp (ref "C60")
      (value "0.1uF")
      (footprint "eagle-import:0805")
      (libsource (lib "eagle-import") (part "SparkFun-Capacitors_510_1.0UF-0805-25V-10%"))
    )
    (comp (ref "C61")
      (value "0.1uF")
      (footprint "eagle-import:0805")
      (libsource (lib "eagle-import") (part "SparkFun-Capacitors_510_1.0UF-0805-25V-10%"))
    )
    (comp (ref "D1")
      (value "250mA/100V")
      (footprint "eagle-import:SOD-323")
      (libsource (lib "eagle-import") (part "DIODE-BAS16J"))
    )
    (comp (ref "D2")
      (value "250mA/100V")
      (footprint "eagle-import:SOD-323")
      (libsource (lib "eagle-import") (part "DIODE-BAS16J"))
    )
    (comp (ref "D3")
      (value "250mA/100V")
      (footprint "eagle-import:SOD-323")
      (libsource (lib "eagle-import") (part "DIODE-BAS16J"))
    )
    (comp (ref "D4")
      (value "250mA/100V")
      (footprint "eagle-import:SOD-323")
      (libsource (lib "eagle-import") (part "DIODE-BAS16J"))
    )
    (comp (ref "D5")
      (value "250mA/100V")
      (footprint "eagle-import:SOD-323")
      (libsource (lib "eagle-import") (part "DIODE-BAS16J"))
    )
    (comp (ref "D6")
      (value "250mA/100V")
      (footprint "eagle-import:SOD-323")
      (libsource (lib "eagle-import") (part "DIODE-BAS16J"))
    )
    (comp (ref "D7")
      (value "250mA/100V")
      (footprint "eagle-import:SOD-323")
      (libsource (lib "eagle-import") (part "DIODE-BAS16J"))
    )
    (comp (ref "LEVEL_SHIFTER1")
      (value "RS0104YQTSSOP-14_JRT-M")
      (footprint "eagle-import:TSSOP-14_JRT-M")
      (fields
        (field (name "MANUFACTURER_PART_NUMBER") "RS0104YQ")
        (field (name "COPYRIGHT") "Copyright (C) 2024 Ultra Librarian. All rights reserved.")
      )
      (libsource (lib "eagle-import") (part "RS0104YQTSSOP-14_JRT-M"))
    )
    (comp (ref "LEVEL_SHIFTER2")
      (value "RS0104YQTSSOP-14_JRT-M")
      (footprint "eagle-import:TSSOP-14_JRT-M")
      (fields
        (field (name "MANUFACTURER_PART_NUMBER") "RS0104YQ")
        (field (name "COPYRIGHT") "Copyright (C) 2024 Ultra Librarian. All rights reserved.")
      )
      (libsource (lib "eagle-import") (part "RS0104YQTSSOP-14_JRT-M"))
    )
    (comp (ref "LEVEL_SHIFTER3")
      (value "RS0104YQTSSOP-14_JRT-M")
      (footprint "eagle-import:TSSOP-14_JRT-M")
      (fields
        (field (name "MANUFACTURER_PART_NUMBER") "RS0104YQ")
        (field (name "COPYRIGHT") "Copyright (C) 2024 Ultra Librarian. All rights reserved.")
      )
      (libsource (lib "eagle-import") (part "RS0104YQTSSOP-14_JRT-M"))
    )
    (comp (ref "LEVEL_SHIFTER4")
      (value "RS0104YQTSSOP-14_JRT-M")
      (footprint "eagle-import:TSSOP-14_JRT-M")
      (fields
        (field (name "MANUFACTURER_PART_NUMBER") "RS0104YQ")
        (field (name "COPYRIGHT") "Copyright (C) 2024 Ultra Librarian. All rights reserved.")
      )
      (libsource (lib "eagle-import") (part "RS0104YQTSSOP-14_JRT-M"))
    )
    (comp (ref "LINE_RECEIVER1")
      (value "SN65LBC175ADD16-M")
      (footprint "eagle-import:D16-M")
      (fields
        (field (name "MANUFACTURER_PART_NUMBER") "SN65LBC175AD")
        (field (name "COPYRIGHT") "Copyright (C) 2024 Ultra Librarian. All rights reserved.")
      )
      (libsource (lib "eagle-import") (part "SN65LBC175ADD16-M"))
    )
    (comp (ref "LINE_RECEIVER2")
      (value "SN65LBC175ADD16-M")
      (footprint "eagle-import:D16-M")
      (fields
        (field (name "MANUFACTURER_PART_NUMBER") "SN65LBC175AD")
        (field (name "COPYRIGHT") "Copyright (C) 2024 Ultra Librarian. All rights reserved.")
      )
      (libsource (lib "eagle-import") (part "SN65LBC175ADD16-M"))
    )
    (comp (ref "LINE_RECEIVER3")
      (value "SN65LBC175ADD16-M")
      (footprint "eagle-import:D16-M")
      (fields
        (field (name "MANUFACTURER_PART_NUMBER") "SN65LBC175AD")
        (field (name "COPYRIGHT") "Copyright (C) 2024 Ultra Librarian. All rights reserved.")
      )
      (libsource (lib "eagle-import") (part "SN65LBC175ADD16-M"))
    )
    (comp (ref "LINE_RECEIVER4")
      (value "SN65LBC175ADD16-M")
      (footprint "eagle-import:D16-M")
      (fields
        (field (name "MANUFACTURER_PART_NUMBER") "SN65LBC175AD")
        (field (name "COPYRIGHT") "Copyright (C) 2024 Ultra Librarian. All rights reserved.")
      )
      (libsource (lib "eagle-import") (part "SN65LBC175ADD16-M"))
    )
    (comp (ref "OPTOCOUPLER")
      (value "ACSL-6400-00TESOIC_6400-00TE-M")
      (footprint "eagle-import:SOIC_6400-00TE-M")
      (fields
        (field (name "MANUFACTURER_PART_NUMBER") "ACSL-6400-00TE")
        (field (name "COPYRIGHT") "Copyright (C) 2024 Ultra Librarian. All rights reserved.")
      )
      (libsource (lib "eagle-import") (part "ACSL-6400-00TESOIC_6400-00TE-M"))
    )
    (comp (ref "OPTOCOUPLER2")
      (value "ACSL-6400-00TESOIC_6400-00TE-M")
      (footprint "eagle-import:SOIC_6400-00TE-M")
      (fields
        (field (name "MANUFACTURER_PART_NUMBER") "ACSL-6400-00TE")
        (field (name "COPYRIGHT") "Copyright (C) 2024 Ultra Librarian. All rights reserved.")
      )
      (libsource (lib "eagle-import") (part "ACSL-6400-00TESOIC_6400-00TE-M"))
    )
    (comp (ref "R17")
      (value "2.25k")
      (footprint "eagle-import:R0805")
      (libsource (lib "eagle-import") (part "R-US_R0805"))
    )
    (comp (ref "R18")
      (value "2.25k")
      (footprint "eagle-import:R0805")
      (libsource (lib "eagle-import") (part "R-US_R0805"))
    )
    (comp (ref "R27")
      (value "2.25k")
      (footprint "eagle-import:R0805")
      (libsource (lib "eagle-import") (part "R-US_R0805"))
    )
    (comp (ref "R28")
      (value "2.25k")
      (footprint "eagle-import:R0805")
      (libsource (lib "eagle-import") (part "R-US_R0805"))
    )
    (comp (ref "R29")
      (value "2.25k")
      (footprint "eagle-import:R0805")
      (libsource (lib "eagle-import") (part "R-US_R0805"))
    )
    (comp (ref "R30")
      (value "2.25k")
      (footprint "eagle-import:R0805")
      (libsource (lib "eagle-import") (part "R-US_R0805"))
    )
    (comp (ref "R31")
      (value "330")
      (footprint "eagle-import:R0805")
      (libsource (lib "eagle-import") (part "R-US_R0805"))
    )
    (comp (ref "R32")
      (value "330")
      (footprint "eagle-import:R0805")
      (libsource (lib "eagle-import") (part "R-US_R0805"))
    )
    (comp (ref "R33")
      (value "330")
      (footprint "eagle-import:R0805")
      (libsource (lib "eagle-import") (part "R-US_R0805"))
    )
    (comp (ref "R34")
      (value "330")
      (footprint "eagle-import:R0805")
      (libsource (lib "eagle-import") (part "R-US_R0805"))
    )
    (comp (ref "R35")
      (value "330")
      (footprint "eagle-import:R0805")
      (libsource (lib "eagle-import") (part "R-US_R0805"))
    )
    (comp (ref "R36")
      (value "330")
      (footprint "eagle-import:R0805")
      (libsource (lib "eagle-import") (part "R-US_R0805"))
    )
    (comp (ref "R37")
      (value "330")
      (footprint "eagle-import:R0805")
      (libsource (lib "eagle-import") (part "R-US_R0805"))
    )
    (comp (ref "R38")
      (value "330")
      (footprint "eagle-import:R0805")
      (libsource (lib "eagle-import") (part "R-US_R0805"))
    )
    (comp (ref "R39")
      (value "500")
      (footprint "eagle-import:R0805")
      (libsource (lib "eagle-import") (part "R-US_R0805"))
    )
    (comp (ref "R40")
      (value "75k")
      (footprint "eagle-import:R0805")
      (libsource (lib "eagle-import") (part "R-US_R0805"))
    )
    (comp (ref "R41")
      (value "25k")
      (footprint "eagle-import:R0805")
      (libsource (lib "eagle-import") (part "R-US_R0805"))
    )
    (comp (ref "R42")
      (value "500")
      (footprint "eagle-import:R0805")
      (libsource (lib "eagle-import") (part "R-US_R0805"))
    )
    (comp (ref "R43")
      (value "75k")
      (footprint "eagle-import:R0805")
      (libsource (lib "eagle-import") (part "R-US_R0805"))
    )
    (comp (ref "R44")
      (value "25k")
      (footprint "eagle-import:R0805")
      (libsource (lib "eagle-import") (part "R-US_R0805"))
    )
    (comp (ref "R45")
      (value "500")
      (footprint "eagle-import:R0805")
      (libsource (lib "eagle-import") (part "R-US_R0805"))
    )
    (comp (ref "R46")
      (value "75k")
      (footprint "eagle-import:R0805")
      (libsource (lib "eagle-import") (part "R-US_R0805"))
    )
    (comp (ref "R47")
      (value "25k")
      (footprint "eagle-import:R0805")
      (libsource (lib "eagle-import") (part "R-US_R0805"))
    )
    (comp (ref "R48")
      (value "2.25k")
      (footprint "eagle-import:R0805")
      (libsource (lib "eagle-import") (part "R-US_R0805"))
    )
    (comp (ref "R49")
      (value "1k")
      (footprint "eagle-import:R0805")
      (libsource (lib "eagle-import") (part "R-US_R0805"))
    )
    (comp (ref "R51")
      (value "500")
      (footprint "eagle-import:R0805")
      (libsource (lib "eagle-import") (part "R-US_R0805"))
    )
    (comp (ref "R52")
      (value "75k")
      (footprint "eagle-import:R0805")
      (libsource (lib "eagle-import") (part "R-US_R0805"))
    )
    (comp (ref "R53")
      (value "25k")
      (footprint "eagle-import:R0805")
      (libsource (lib "eagle-import") (part "R-US_R0805"))
    )
    (comp (ref "R54")
      (value "500")
      (footprint "eagle-import:R0805")
      (libsource (lib "eagle-import") (part "R-US_R0805"))
    )
    (comp (ref "R55")
      (value "75k")
      (footprint "eagle-import:R0805")
      (libsource (lib "eagle-import") (part "R-US_R0805"))
    )
    (comp (ref "R56")
      (value "25k")
      (footprint "eagle-import:R0805")
      (libsource (lib "eagle-import") (part "R-US_R0805"))
    )
    (comp (ref "R57")
      (value "500")
      (footprint "eagle-import:R0805")
      (libsource (lib "eagle-import") (part "R-US_R0805"))
    )
    (comp (ref "R58")
      (value "75k")
      (footprint "eagle-import:R0805")
      (libsource (lib "eagle-import") (part "R-US_R0805"))
    )
    (comp (ref "R59")
      (value "25k")
      (footprint "eagle-import:R0805")
      (libsource (lib "eagle-import") (part "R-US_R0805"))
    )
    (comp (ref "R63")
      (value "1k")
      (footprint "eagle-import:R0805")
      (libsource (lib "eagle-import") (part "R-US_R0805"))
    )
    (comp (ref "R64")
      (value "1k")
      (footprint "eagle-import:R0805")
      (libsource (lib "eagle-import") (part "R-US_R0805"))
    )
    (comp (ref "R65")
      (value "1k")
      (footprint "eagle-import:R0805")
      (libsource (lib "eagle-import") (part "R-US_R0805"))
    )
    (comp (ref "R66")
      (value "1k")
      (footprint "eagle-import:R0805")
      (libsource (lib "eagle-import") (part "R-US_R0805"))
    )
    (comp (ref "R67")
      (value "1k")
      (footprint "eagle-import:R0805")
      (libsource (lib "eagle-import") (part "R-US_R0805"))
    )
    (comp (ref "R68")
      (value "1k")
      (footprint "eagle-import:R0805")
      (libsource (lib "eagle-import") (part "R-US_R0805"))
    )
    (comp (ref "R79")
      (value "10k")
      (footprint "eagle-import:R0805")
      (libsource (lib "eagle-import") (part "R-US_R0805"))
    )
    (comp (ref "R80")
      (value "10k")
      (footprint "eagle-import:R0805")
      (libsource (lib "eagle-import") (part "R-US_R0805"))
    )
    (comp (ref "R81")
      (value "10k")
      (footprint "eagle-import:R0805")
      (libsource (lib "eagle-import") (part "R-US_R0805"))
    )
    (comp (ref "R82")
      (value "10k")
      (footprint "eagle-import:R0805")
      (libsource (lib "eagle-import") (part "R-US_R0805"))
    )
    (comp (ref "R83")
      (value "10k")
      (footprint "eagle-import:R0805")
      (libsource (lib "eagle-import") (part "R-US_R0805"))
    )
    (comp (ref "R84")
      (value "10k")
      (footprint "eagle-import:R0805")
      (libsource (lib "eagle-import") (part "R-US_R0805"))
    )
    (comp (ref "R85")
      (value "10k")
      (footprint "eagle-import:R0805")
      (libsource (lib "eagle-import") (part "R-US_R0805"))
    )
    (comp (ref "R86")
      (value "10k")
      (footprint "eagle-import:R0805")
      (libsource (lib "eagle-import") (part "R-US_R0805"))
    )
    (comp (ref "R87")
      (value "10k")
      (footprint "eagle-import:R0805")
      (libsource (lib "eagle-import") (part "R-US_R0805"))
    )
    (comp (ref "R88")
      (value "10k")
      (footprint "eagle-import:R0805")
      (libsource (lib "eagle-import") (part "R-US_R0805"))
    )
    (comp (ref "R89")
      (value "10k")
      (footprint "eagle-import:R0805")
      (libsource (lib "eagle-import") (part "R-US_R0805"))
    )
    (comp (ref "R90")
      (value "10k")
      (footprint "eagle-import:R0805")
      (libsource (lib "eagle-import") (part "R-US_R0805"))
    )
    (comp (ref "R91")
      (value "10k")
      (footprint "eagle-import:R0805")
      (libsource (lib "eagle-import") (part "R-US_R0805"))
    )
    (comp (ref "R92")
      (value "10k")
      (footprint "eagle-import:R0805")
      (libsource (lib "eagle-import") (part "R-US_R0805"))
    )
  )
  (nets
    (net (code "1") (name "+3.3V") (class "Default")
      (node (ref "C15") (pin "2") (pinfunction "2_2") (pintype "passive"))
      (node (ref "C16") (pin "2") (pinfunction "2_2") (pintype "passive"))
      (node (ref "C17") (pin "2") (pinfunction "2_2") (pintype "passive"))
      (node (ref "C18") (pin "2") (pinfunction "2_2") (pintype "passive"))
      (node (ref "C19") (pin "2") (pinfunction "2_2") (pintype "passive"))
      (node (ref "C20") (pin "2") (pinfunction "2_2") (pintype "passive"))
      (node (ref "C21") (pin "2") (pinfunction "2_2") (pintype "passive"))
      (node (ref "C22") (pin "2") (pinfunction "2_2") (pintype "passive"))
      (node (ref "C23") (pin "2") (pinfunction "2_2") (pintype "passive"))
      (node (ref "C24") (pin "2") (pinfunction "2_2") (pintype "passive"))
      (node (ref "C25") (pin "2") (pinfunction "2_2") (pintype "passive"))
      (node (ref "C26") (pin "2") (pinfunction "2_2") (pintype "passive"))
      (node (ref "C27") (pin "2") (pinfunction "2_2") (pintype "passive"))
      (node (ref "C28") (pin "2") (pinfunction "2_2") (pintype "passive"))
      (node (ref "C29") (pin "2") (pinfunction "2_2") (pintype "passive"))
      (node (ref "C30") (pin "2") (pinfunction "2_2") (pintype "passive"))
      (node (ref "C31") (pin "2") (pinfunction "2_2") (pintype "passive"))
      (node (ref "C36") (pin "2") (pinfunction "2_2") (pintype "passive"))
      (node (ref "C4") (pin "2") (pinfunction "2_2") (pintype "passive"))
      (node (ref "C6") (pin "1") (pinfunction "1_1") (pintype "passive"))
      (node (ref "C60") (pin "2") (pinfunction "2_2") (pintype "passive"))
      (node (ref "C61") (pin "2") (pinfunction "2_2") (pintype "passive"))
      (node (ref "L5") (pin "2") (pinfunction "2_2") (pintype "passive"))
      (node (ref "LDO") (pin "2") (pinfunction "OUT_2_2") (pintype "output"))
      (node (ref "LDO") (pin "4") (pinfunction "OUT_4_4") (pintype "output"))
      (node (ref "LEVEL_SHIFTER1") (pin "14") (pinfunction "VCCB_14") (pintype "power_in"))
      (node (ref "LEVEL_SHIFTER2") (pin "14") (pinfunction "VCCB_14") (pintype "power_in"))
      (node (ref "LEVEL_SHIFTER3") (pin "14") (pinfunction "VCCB_14") (pintype "power_in"))
      (node (ref "LEVEL_SHIFTER4") (pin "14") (pinfunction "VCCB_14") (pintype "power_in"))
      (node (ref "OPTOCOUPLER") (pin "10") (pinfunction "VDD_2_10") (pintype "power_in"))
      (node (ref "OPTOCOUPLER") (pin "15") (pinfunction "VDD_15") (pintype "power_in"))
      (node (ref "OPTOCOUPLER2") (pin "10") (pinfunction "VDD_2_10") (pintype "power_in"))
      (node (ref "OPTOCOUPLER2") (pin "15") (pinfunction "VDD_15") (pintype "power_in"))
      (node (ref "OSCILLATOR") (pin "1") (pinfunction "V+_1") (pintype "power_in"))
      (node (ref "R21") (pin "1") (pinfunction "1_1") (pintype "passive"))
      (node (ref "R49") (pin "2") (pinfunction "2_2") (pintype "passive"))
      (node (ref "R63") (pin "2") (pinfunction "2_2") (pintype "passive"))
      (node (ref "R64") (pin "2") (pinfunction "2_2") (pintype "passive"))
      (node (ref "R65") (pin "2") (pinfunction "2_2") (pintype "passive"))
      (node (ref "R66") (pin "2") (pinfunction "2_2") (pintype "passive"))
      (node (ref "R67") (pin "2") (pinfunction "2_2") (pintype "passive"))
      (node (ref "R68") (pin "2") (pinfunction "2_2") (pintype "passive"))
      (node (ref "R69") (pin "2") (pinfunction "2_2") (pintype "passive"))
      (node (ref "STM32F2") (pin "100") (pinfunction "VDD_100") (pintype "power_in"))
      (node (ref "STM32F2") (pin "11") (pinfunction "VDD_2_11") (pintype "power_in"))
      (node (ref "STM32F2") (pin "19") (pinfunction "VDD_3_19") (pintype "power_in"))
      (node (ref "STM32F2") (pin "21") (pinfunction "VREF+_21") (pintype "power_in"))
      (node (ref "STM32F2") (pin "28") (pinfunction "VDD_4_28") (pintype "power_in"))
      (node (ref "STM32F2") (pin "50") (pinfunction "VDD_5_50") (pintype "power_in"))
      (node (ref "STM32F2") (pin "6") (pinfunction "VBAT_6") (pintype "power_in"))
      (node (ref "STM32F2") (pin "75") (pinfunction "VDD_6_75") (pintype "power_in"))
      (node (ref "TP3") (pin "1") (pinfunction "1_1") (pintype "bidirectional"))
    )
    (net (code "2") (name "+3.3VA") (class "Default")
      (node (ref "C32") (pin "2") (pinfunction "2_2") (pintype "passive"))
      (node (ref "C33") (pin "2") (pinfunction "2_2") (pintype "passive"))
      (node (ref "L5") (pin "1") (pinfunction "1_1") (pintype "passive"))
      (node (ref "STM32F2") (pin "22") (pinfunction "VDDA_22") (pintype "power_in"))
    )
    (net (code "3") (name "+5V") (class "Default")
      (node (ref "10UH_L1") (pin "2") (pinfunction "2_2") (pintype "passive"))
      (node (ref "330UF_C3") (pin "1") (pinfunction "1_1") (pintype "passive"))
      (node (ref "5V") (pin "6") (pinfunction "FB_6") (pintype "passive"))
      (node (ref "C46") (pin "2") (pinfunction "2_2") (pintype "passive"))
      (node (ref "C47") (pin "2") (pinfunction "2_2") (pintype "passive"))
      (node (ref "C48") (pin "2") (pinfunction "2_2") (pintype "passive"))
      (node (ref "C49") (pin "2") (pinfunction "2_2") (pintype "passive"))
      (node (ref "C5") (pin "1") (pinfunction "1_1") (pintype "passive"))
      (node (ref "C54") (pin "2") (pinfunction "2_2") (pintype "passive"))
      (node (ref "C59") (pin "2") (pinfunction "2_2") (pintype "passive"))
      (node (ref "LDO") (pin "3") (pinfunction "IN_3") (pintype "input"))
      (node (ref "LEVEL_SHIFTER1") (pin "1") (pinfunction "VCCA_1") (pintype "power_in"))
      (node (ref "LEVEL_SHIFTER1") (pin "8") (pinfunction "OE_8") (pintype "input"))
      (node (ref "LEVEL_SHIFTER2") (pin "1") (pinfunction "VCCA_1") (pintype "power_in"))
      (node (ref "LEVEL_SHIFTER2") (pin "8") (pinfunction "OE_8") (pintype "input"))
      (node (ref "LEVEL_SHIFTER3") (pin "1") (pinfunction "VCCA_1") (pintype "power_in"))
      (node (ref "LEVEL_SHIFTER3") (pin "8") (pinfunction "OE_8") (pintype "input"))
      (node (ref "LEVEL_SHIFTER4") (pin "1") (pinfunction "VCCA_1") (pintype "power_in"))
      (node (ref "LEVEL_SHIFTER4") (pin "8") (pinfunction "OE_8") (pintype "input"))
      (node (ref "LINE_DRIVER1") (pin "20") (pinfunction "VCC_20") (pintype "power_in"))
      (node (ref "LINE_DRIVER2") (pin "20") (pinfunction "VCC_20") (pintype "power_in"))
      (node (ref "LINE_RECEIVER1") (pin "16") (pinfunction "VCC_16") (pintype "power_in"))
      (node (ref "LINE_RECEIVER2") (pin "16") (pinfunction "VCC_16") (pintype "power_in"))
      (node (ref "LINE_RECEIVER3") (pin "16") (pinfunction "VCC_16") (pintype "power_in"))
      (node (ref "LINE_RECEIVER4") (pin "16") (pinfunction "VCC_16") (pintype "power_in"))
      (node (ref "R19") (pin "1") (pinfunction "1_1") (pintype "passive"))
      (node (ref "R24") (pin "2") (pinfunction "2_2") (pintype "passive"))
      (node (ref "R26") (pin "2") (pinfunction "2_2") (pintype "passive"))
      (node (ref "R6") (pin "2") (pinfunction "2_2") (pintype "passive"))
      (node (ref "R71") (pin "2") (pinfunction "2_2") (pintype "passive"))
      (node (ref "R73") (pin "2") (pinfunction "2_2") (pintype "passive"))
      (node (ref "R75") (pin "2") (pinfunction "2_2") (pintype "passive"))
      (node (ref "TP1") (pin "1") (pinfunction "1_1") (pintype "bidirectional"))
    )
    (net (code "4") (name "+14V") (class "Default")
      (node (ref "-15V") (pin "12") (pinfunction "EN_12") (pintype "input"))
      (node (ref "-15V") (pin "13") (pinfunction "VIN_2_13") (pintype "input"))
      (node (ref "-15V") (pin "14") (pinfunction "VIN_14") (pintype "input"))
      (node (ref "14_JACK") (pin "1") (pinfunction "1_1") (pintype "passive"))
      (node (ref "180UF") (pin "1") (pinfunction "1_1") (pintype "passive"))
      (node (ref "5V") (pin "2") (pinfunction "VIN_2") (pintype "input"))
      (node (ref "C1") (pin "2") (pinfunction "2_2") (pintype "passive"))
      (node (ref "C8") (pin "1") (pinfunction "1_1") (pintype "passive"))
      (node (ref "C9") (pin "2") (pinfunction "2_2") (pintype "passive"))
      (node (ref "OP_AMP") (pin "4") (pinfunction "V+_4") (pintype "output"))
      (node (ref "R2") (pin "2") (pinfunction "2_2") (pintype "passive"))
      (node (ref "R22") (pin "1") (pinfunction "1_1") (pintype "passive"))
      (node (ref "R39") (pin "2") (pinfunction "2_2") (pintype "passive"))
      (node (ref "R40") (pin "2") (pinfunction "2_2") (pintype "passive"))
      (node (ref "R42") (pin "2") (pinfunction "2_2") (pintype "passive"))
      (node (ref "R43") (pin "2") (pinfunction "2_2") (pintype "passive"))
      (node (ref "R45") (pin "2") (pinfunction "2_2") (pintype "passive"))
      (node (ref "R46") (pin "2") (pinfunction "2_2") (pintype "passive"))
      (node (ref "R51") (pin "2") (pinfunction "2_2") (pintype "passive"))
      (node (ref "R52") (pin "2") (pinfunction "2_2") (pintype "passive"))
      (node (ref "R54") (pin "2") (pinfunction "2_2") (pintype "passive"))
      (node (ref "R55") (pin "2") (pinfunction "2_2") (pintype "passive"))
      (node (ref "R57") (pin "2") (pinfunction "2_2") (pintype "passive"))
      (node (ref "R58") (pin "2") (pinfunction "2_2") (pintype "passive"))
      (node (ref "R8") (pin "2") (pinfunction "2_2") (pintype "passive"))
      (node (ref "TP4") (pin "1") (pinfunction "1_1") (pintype "bidirectional"))
    )
    (net (code "5") (name "+24V") (class "Default")
      (node (ref "J1") (pin "1") (pinfunction "1_1") (pintype "passive"))
      (node (ref "J3") (pin "47") (pinfunction "47_47") (pintype "passive"))
      (node (ref "J4") (pin "47") (pinfunction "47_47") (pintype "passive"))
      (node (ref "NPN") (pin "9") (pinfunction "COM_9") (pintype "bidirectional"))
      (node (ref "NPN2") (pin "9") (pinfunction "COM_9") (pintype "bidirectional"))
      (node (ref "R17") (pin "2") (pinfunction "2_2") (pintype "passive"))
      (node (ref "R18") (pin "2") (pinfunction "2_2") (pintype "passive"))
      (node (ref "R27") (pin "2") (pinfunction "2_2") (pintype "passive"))
      (node (ref "R28") (pin "2") (pinfunction "2_2") (pintype "passive"))
      (node (ref "R29") (pin "2") (pinfunction "2_2") (pintype "passive"))
      (node (ref "R30") (pin "2") (pinfunction "2_2") (pintype "passive"))
      (node (ref "R48") (pin "2") (pinfunction "2_2") (pintype "passive"))
    )
    (net (code "6") (name "-15V") (class "Default")
      (node (ref "-15V") (pin "10") (pinfunction "AGND_10") (pintype "power_in"))
      (node (ref "-15V") (pin "15") (pinfunction "PGND_2_15") (pintype "power_in"))
      (node (ref "-15V") (pin "16") (pinfunction "PGND_16") (pintype "power_in"))
      (node (ref "-15V") (pin "EPAD") (pinfunction "EPAD_EPAD") (pintype "passive"))
      (node (ref "C10") (pin "1") (pinfunction "1_1") (pintype "passive"))
      (node (ref "C12") (pin "1") (pinfunction "1_1") (pintype "passive"))
      (node (ref "C14") (pin "1") (pinfunction "1_1") (pintype "passive"))
      (node (ref "C9") (pin "1") (pinfunction "1_1") (pintype "passive"))
      (node (ref "LED2") (pin "C") (pinfunction "C_C") (pintype "passive"))
      (node (ref "OP_AMP") (pin "11") (pinfunction "V-_11") (pintype "output"))
      (node (ref "R4") (pin "1") (pinfunction "1_1") (pintype "passive"))
      (node (ref "TP2") (pin "1") (pinfunction "1_1") (pintype "bidirectional"))
    )
    (net (code "7") (name "1.65V") (class "Default")
      (node (ref "J2") (pin "3") (pinfunction "3_3") (pintype "bidirectional"))
      (node (ref "J5") (pin "3") (pinfunction "3_3") (pintype "bidirectional"))
      (node (ref "OP_AMP") (pin "3") (pinfunction "+IN_1_3") (pintype "output"))
      (node (ref "R7") (pin "2") (pinfunction "2_2") (pintype "passive"))
    )
    (net (code "8") (name "1.65V_REF") (class "Default")
      (node (ref "OP_AMP") (pin "1") (pinfunction "OUT_1_1") (pintype "output"))
      (node (ref "OP_AMP") (pin "2") (pinfunction "-IN_1_2") (pintype "output"))
      (node (ref "R13") (pin "1") (pinfunction "1_1") (pintype "passive"))
      (node (ref "R9") (pin "1") (pinfunction "1_1") (pintype "passive"))
    )
    (net (code "9") (name "ABS_ENC_OUT_GPIO_1") (class "Default")
      (node (ref "LEVEL_SHIFTER2") (pin "10") (pinfunction "B4_10") (pintype "bidirectional"))
      (node (ref "STM32F2") (pin "45") (pinfunction "PE14_45") (pintype "bidirectional"))
    )
    (net (code "10") (name "ABS_ENC_OUT_GPIO_1_5V") (class "Default")
      (node (ref "LEVEL_SHIFTER2") (pin "5") (pinfunction "A4_5") (pintype "bidirectional"))
      (node (ref "LINE_RECEIVER1") (pin "13") (pinfunction "4Y_13") (pintype "output"))
      (node (ref "R92") (pin "2") (pinfunction "2_2") (pintype "passive"))
    )
    (net (code "11") (name "ABS_ENC_OUT_GPIO_2") (class "Default")
      (node (ref "LEVEL_SHIFTER3") (pin "10") (pinfunction "B4_10") (pintype "bidirectional"))
      (node (ref "STM32F2") (pin "92") (pinfunction "PB6_92") (pintype "bidirectional"))
    )
    (net (code "12") (name "ABS_ENC_OUT_GPIO_2_5V") (class "Default")
      (node (ref "LEVEL_SHIFTER3") (pin "5") (pinfunction "A4_5") (pintype "bidirectional"))
      (node (ref "LINE_RECEIVER3") (pin "13") (pinfunction "4Y_13") (pintype "output"))
      (node (ref "R88") (pin "2") (pinfunction "2_2") (pintype "passive"))
    )
    (net (code "13") (name "ABS_ENC_OUT_HI_1") (class "Default")
      (node (ref "J3") (pin "48") (pinfunction "48_48") (pintype "passive"))
      (node (ref "LINE_RECEIVER1") (pin "14") (pinfunction "4A_14") (pintype "input"))
      (node (ref "R33") (pin "1") (pinfunction "1_1") (pintype "passive"))
    )
    (net (code "14") (name "ABS_ENC_OUT_HI_2") (class "Default")
      (node (ref "J4") (pin "48") (pinfunction "48_48") (pintype "passive"))
      (node (ref "LINE_RECEIVER3") (pin "14") (pinfunction "4A_14") (pintype "input"))
      (node (ref "R37") (pin "1") (pinfunction "1_1") (pintype "passive"))
    )
    (net (code "15") (name "ABS_ENC_OUT_LO_1") (class "Default")
      (node (ref "J3") (pin "49") (pinfunction "49_49") (pintype "passive"))
      (node (ref "LINE_RECEIVER1") (pin "15") (pinfunction "4B_15") (pintype "input"))
      (node (ref "R33") (pin "2") (pinfunction "2_2") (pintype "passive"))
    )
    (net (code "16") (name "ABS_ENC_OUT_LO_2") (class "Default")
      (node (ref "J4") (pin "49") (pinfunction "49_49") (pintype "passive"))
      (node (ref "LINE_RECEIVER3") (pin "15") (pinfunction "4B_15") (pintype "input"))
      (node (ref "R37") (pin "2") (pinfunction "2_2") (pintype "passive"))
    )
    (net (code "17") (name "ALARM_RST_AN_1") (class "Default")
      (node (ref "J3") (pin "44") (pinfunction "44_44") (pintype "passive"))
      (node (ref "NPN") (pin "14") (pinfunction "3C_14") (pintype "output"))
    )
    (net (code "18") (name "ALARM_RST_AN_2") (class "Default")
      (node (ref "J4") (pin "44") (pinfunction "44_44") (pintype "passive"))
      (node (ref "NPN2") (pin "12") (pinfunction "5C_12") (pintype "output"))
    )
    (net (code "19") (name "ALARM_RST_GPIO_1") (class "Default")
      (node (ref "NPN") (pin "3") (pinfunction "3B_3") (pintype "input"))
      (node (ref "STM32F2") (pin "38") (pinfunction "PE7_38") (pintype "bidirectional"))
    )
    (net (code "20") (name "ALARM_RST_GPIO_2") (class "Default")
      (node (ref "NPN2") (pin "5") (pinfunction "5B_5") (pintype "input"))
      (node (ref "STM32F2") (pin "84") (pinfunction "PD3_84") (pintype "bidirectional"))
    )
    (net (code "21") (name "ALO1_LED") (class "Default")
      (node (ref "R61") (pin "1") (pinfunction "1_1") (pintype "passive"))
      (node (ref "STM32F2") (pin "1") (pinfunction "PE2_1") (pintype "bidirectional"))
    )
    (net (code "22") (name "ALO2_LED") (class "Default")
      (node (ref "R62") (pin "1") (pinfunction "1_1") (pintype "passive"))
      (node (ref "STM32F2") (pin "2") (pinfunction "PE3_2") (pintype "bidirectional"))
    )
    (net (code "23") (name "ALO3_LED") (class "Default")
      (node (ref "R77") (pin "1") (pinfunction "1_1") (pintype "passive"))
      (node (ref "STM32F2") (pin "3") (pinfunction "PE4_3") (pintype "bidirectional"))
    )
    (net (code "24") (name "ALO_AN_A_1") (class "Default")
      (node (ref "D1") (pin "A") (pinfunction "A_A") (pintype "passive"))
      (node (ref "J3") (pin "37") (pinfunction "37_37") (pintype "passive"))
      (node (ref "OPTOCOUPLER") (pin "2") (pinfunction "CATHODE1_2") (pintype "bidirectional"))
    )
    (net (code "25") (name "ALO_AN_A_2") (class "Default")
      (node (ref "D4") (pin "A") (pinfunction "A_A") (pintype "passive"))
      (node (ref "J4") (pin "37") (pinfunction "37_37") (pintype "passive"))
      (node (ref "OPTOCOUPLER2") (pin "2") (pinfunction "CATHODE1_2") (pintype "bidirectional"))
    )
    (net (code "26") (name "ALO_AN_B_1") (class "Default")
      (node (ref "D2") (pin "A") (pinfunction "A_A") (pintype "passive"))
      (node (ref "J3") (pin "38") (pinfunction "38_38") (pintype "passive"))
      (node (ref "OPTOCOUPLER") (pin "4") (pinfunction "CATHODE2_4") (pintype "bidirectional"))
    )
    (net (code "27") (name "ALO_AN_B_2") (class "Default")
      (node (ref "D5") (pin "A") (pinfunction "A_A") (pintype "passive"))
      (node (ref "J4") (pin "38") (pinfunction "38_38") (pintype "passive"))
      (node (ref "OPTOCOUPLER2") (pin "4") (pinfunction "CATHODE2_4") (pintype "bidirectional"))
    )
    (net (code "28") (name "ALO_AN_C_1") (class "Default")
      (node (ref "D3") (pin "A") (pinfunction "A_A") (pintype "passive"))
      (node (ref "J3") (pin "39") (pinfunction "39_39") (pintype "passive"))
      (node (ref "OPTOCOUPLER") (pin "6") (pinfunction "CATHODE3_6") (pintype "bidirectional"))
    )
    (net (code "29") (name "ALO_AN_C_2") (class "Default")
      (node (ref "D6") (pin "A") (pinfunction "A_A") (pintype "passive"))
      (node (ref "J4") (pin "39") (pinfunction "39_39") (pintype "passive"))
      (node (ref "OPTOCOUPLER2") (pin "6") (pinfunction "CATHODE3_6") (pintype "bidirectional"))
    )
    (net (code "30") (name "ALO_GPIO_A_1") (class "Default")
      (node (ref "OPTOCOUPLER") (pin "14") (pinfunction "V01_14") (pintype "bidirectional"))
      (node (ref "R66") (pin "1") (pinfunction "1_1") (pintype "passive"))
      (node (ref "STM32F2") (pin "31") (pinfunction "PA6_31") (pintype "bidirectional"))
    )
    (net (code "31") (name "ALO_GPIO_A_2") (class "Default")
      (node (ref "OPTOCOUPLER2") (pin "14") (pinfunction "V01_14") (pintype "bidirectional"))
      (node (ref "R63") (pin "1") (pinfunction "1_1") (pintype "passive"))
      (node (ref "STM32F2") (pin "77") (pinfunction "PA15_77") (pintype "bidirectional"))
    )
    (net (code "32") (name "ALO_GPIO_B_1") (class "Default")
      (node (ref "OPTOCOUPLER") (pin "13") (pinfunction "V02_13") (pintype "bidirectional"))
      (node (ref "R67") (pin "1") (pinfunction "1_1") (pintype "passive"))
      (node (ref "STM32F2") (pin "32") (pinfunction "PA7_32") (pintype "bidirectional"))
    )
    (net (code "33") (name "ALO_GPIO_B_2") (class "Default")
      (node (ref "OPTOCOUPLER2") (pin "13") (pinfunction "V02_13") (pintype "bidirectional"))
      (node (ref "R64") (pin "1") (pinfunction "1_1") (pintype "passive"))
      (node (ref "STM32F2") (pin "78") (pinfunction "PC10_78") (pintype "bidirectional"))
    )
    (net (code "34") (name "ALO_GPIO_C_1") (class "Default")
      (node (ref "OPTOCOUPLER") (pin "12") (pinfunction "V03_12") (pintype "bidirectional"))
      (node (ref "R68") (pin "1") (pinfunction "1_1") (pintype "passive"))
      (node (ref "STM32F2") (pin "33") (pinfunction "PC4_33") (pintype "bidirectional"))
    )
    (net (code "35") (name "ALO_GPIO_C_2") (class "Default")
      (node (ref "OPTOCOUPLER2") (pin "12") (pinfunction "V03_12") (pintype "bidirectional"))
      (node (ref "R65") (pin "1") (pinfunction "1_1") (pintype "passive"))
      (node (ref "STM32F2") (pin "79") (pinfunction "PC11_79") (pintype "bidirectional"))
    )
    (net (code "36") (name "CLR_GPIO_1") (class "Default")
      (node (ref "LINE_DRIVER1") (pin "11") (pinfunction "3A_11") (pintype "input"))
      (node (ref "STM32F2") (pin "55") (pinfunction "PD8_55") (pintype "bidirectional"))
    )
    (net (code "37") (name "CLR_GPIO_2") (class "Default")
      (node (ref "LINE_DRIVER2") (pin "11") (pinfunction "3A_11") (pintype "input"))
      (node (ref "STM32F2") (pin "69") (pinfunction "PA10_69") (pintype "bidirectional"))
    )
    (net (code "38") (name "CLR_HI_1") (class "Default")
      (node (ref "J3") (pin "15") (pinfunction "15_15") (pintype "passive"))
      (node (ref "LINE_DRIVER1") (pin "12") (pinfunction "3Y_12") (pintype "output"))
    )
    (net (code "39") (name "CLR_HI_2") (class "Default")
      (node (ref "J4") (pin "15") (pinfunction "15_15") (pintype "passive"))
      (node (ref "LINE_DRIVER2") (pin "12") (pinfunction "3Y_12") (pintype "output"))
    )
    (net (code "40") (name "CLR_LO_1") (class "Default")
      (node (ref "J3") (pin "14") (pinfunction "14_14") (pintype "passive"))
      (node (ref "LINE_DRIVER1") (pin "14") (pinfunction "3Z_14") (pintype "output"))
    )
    (net (code "41") (name "CLR_LO_2") (class "Default")
      (node (ref "J4") (pin "14") (pinfunction "14_14") (pintype "passive"))
      (node (ref "LINE_DRIVER2") (pin "14") (pinfunction "3Z_14") (pintype "output"))
    )
    (net (code "42") (name "DAC_1_IN") (class "Default")
      (node (ref "J2") (pin "2") (pinfunction "2_2") (pintype "bidirectional"))
      (node (ref "R11") (pin "1") (pinfunction "1_1") (pintype "passive"))
    )
    (net (code "43") (name "DAC_2_IN") (class "Default")
      (node (ref "J5") (pin "2") (pinfunction "2_2") (pintype "bidirectional"))
      (node (ref "R16") (pin "1") (pinfunction "1_1") (pintype "passive"))
    )
    (net (code "44") (name "DIR_GPIO_1") (class "Default")
      (node (ref "LINE_DRIVER1") (pin "9") (pinfunction "2A_9") (pintype "input"))
      (node (ref "STM32F2") (pin "54") (pinfunction "PB15_54") (pintype "bidirectional"))
    )
    (net (code "45") (name "DIR_GPIO_2") (class "Default")
      (node (ref "LINE_DRIVER2") (pin "9") (pinfunction "2A_9") (pintype "input"))
      (node (ref "STM32F2") (pin "71") (pinfunction "PA12_71") (pintype "bidirectional"))
    )
    (net (code "46") (name "DIR_HI_1") (class "Default")
      (node (ref "J3") (pin "11") (pinfunction "11_11") (pintype "passive"))
      (node (ref "LINE_DRIVER1") (pin "8") (pinfunction "2Y_8") (pintype "output"))
    )
    (net (code "47") (name "DIR_HI_2") (class "Default")
      (node (ref "J4") (pin "11") (pinfunction "11_11") (pintype "passive"))
      (node (ref "LINE_DRIVER2") (pin "8") (pinfunction "2Y_8") (pintype "output"))
    )
    (net (code "48") (name "DIR_LO_1") (class "Default")
      (node (ref "J3") (pin "12") (pinfunction "12_12") (pintype "passive"))
      (node (ref "LINE_DRIVER1") (pin "6") (pinfunction "2Z_6") (pintype "output"))
    )
    (net (code "49") (name "DIR_LO_2") (class "Default")
      (node (ref "J4") (pin "12") (pinfunction "12_12") (pintype "passive"))
      (node (ref "LINE_DRIVER2") (pin "6") (pinfunction "2Z_6") (pintype "output"))
    )
    (net (code "50") (name "ENC_PUL_OUT_A_GPIO_1") (class "Default")
      (node (ref "LEVEL_SHIFTER2") (pin "13") (pinfunction "B1_13") (pintype "bidirectional"))
      (node (ref "STM32F2") (pin "59") (pinfunction "PD12_59") (pintype "bidirectional"))
    )
    (net (code "51") (name "ENC_PUL_OUT_A_GPIO_1_5V") (class "Default")
      (node (ref "LEVEL_SHIFTER2") (pin "2") (pinfunction "A1_2") (pintype "bidirectional"))
      (node (ref "LINE_RECEIVER1") (pin "3") (pinfunction "1Y_3") (pintype "output"))
      (node (ref "R91") (pin "2") (pinfunction "2_2") (pintype "passive"))
    )
    (net (code "52") (name "ENC_PUL_OUT_A_GPIO_2") (class "Default")
      (node (ref "LEVEL_SHIFTER3") (pin "13") (pinfunction "B1_13") (pintype "bidirectional"))
      (node (ref "STM32F2") (pin "89") (pinfunction "PB3_89") (pintype "bidirectional"))
    )
    (net (code "53") (name "ENC_PUL_OUT_A_GPIO_2_5V") (class "Default")
      (node (ref "LEVEL_SHIFTER3") (pin "2") (pinfunction "A1_2") (pintype "bidirectional"))
      (node (ref "LINE_RECEIVER3") (pin "3") (pinfunction "1Y_3") (pintype "output"))
      (node (ref "R87") (pin "2") (pinfunction "2_2") (pintype "passive"))
    )
    (net (code "54") (name "ENC_PUL_OUT_A_HI_1") (class "Default")
      (node (ref "J3") (pin "33") (pinfunction "33_33") (pintype "passive"))
      (node (ref "LINE_RECEIVER1") (pin "2") (pinfunction "1A_2") (pintype "input"))
      (node (ref "R31") (pin "1") (pinfunction "1_1") (pintype "passive"))
    )
    (net (code "55") (name "ENC_PUL_OUT_A_HI_2") (class "Default")
      (node (ref "J4") (pin "33") (pinfunction "33_33") (pintype "passive"))
      (node (ref "LINE_RECEIVER3") (pin "2") (pinfunction "1A_2") (pintype "input"))
      (node (ref "R35") (pin "1") (pinfunction "1_1") (pintype "passive"))
    )
    (net (code "56") (name "ENC_PUL_OUT_A_LO_1") (class "Default")
      (node (ref "J3") (pin "34") (pinfunction "34_34") (pintype "passive"))
      (node (ref "LINE_RECEIVER1") (pin "1") (pinfunction "1B_1") (pintype "input"))
      (node (ref "R31") (pin "2") (pinfunction "2_2") (pintype "passive"))
    )
    (net (code "57") (name "ENC_PUL_OUT_A_LO_2") (class "Default")
      (node (ref "J4") (pin "34") (pinfunction "34_34") (pintype "passive"))
      (node (ref "LINE_RECEIVER3") (pin "1") (pinfunction "1B_1") (pintype "input"))
      (node (ref "R35") (pin "2") (pinfunction "2_2") (pintype "passive"))
    )
    (net (code "58") (name "ENC_PUL_OUT_B_GPIO_1") (class "Default")
      (node (ref "LEVEL_SHIFTER2") (pin "12") (pinfunction "B2_12") (pintype "bidirectional"))
      (node (ref "STM32F2") (pin "42") (pinfunction "PE11_42") (pintype "bidirectional"))
    )
    (net (code "59") (name "ENC_PUL_OUT_B_GPIO_1_5V") (class "Default")
      (node (ref "LEVEL_SHIFTER2") (pin "3") (pinfunction "A2_3") (pintype "bidirectional"))
      (node (ref "LINE_RECEIVER1") (pin "5") (pinfunction "2Y_5") (pintype "output"))
      (node (ref "R90") (pin "2") (pinfunction "2_2") (pintype "passive"))
    )
    (net (code "60") (name "ENC_PUL_OUT_B_GPIO_2") (class "Default")
      (node (ref "LEVEL_SHIFTER3") (pin "12") (pinfunction "B2_12") (pintype "bidirectional"))
      (node (ref "STM32F2") (pin "90") (pinfunction "PB4_90") (pintype "bidirectional"))
    )
    (net (code "61") (name "ENC_PUL_OUT_B_GPIO_2_5V") (class "Default")
      (node (ref "LEVEL_SHIFTER3") (pin "3") (pinfunction "A2_3") (pintype "bidirectional"))
      (node (ref "LINE_RECEIVER3") (pin "5") (pinfunction "2Y_5") (pintype "output"))
      (node (ref "R86") (pin "2") (pinfunction "2_2") (pintype "passive"))
    )
    (net (code "62") (name "ENC_PUL_OUT_B_HI_1") (class "Default")
      (node (ref "J3") (pin "35") (pinfunction "35_35") (pintype "passive"))
      (node (ref "LINE_RECEIVER1") (pin "6") (pinfunction "2A_6") (pintype "input"))
      (node (ref "R32") (pin "2") (pinfunction "2_2") (pintype "passive"))
    )
    (net (code "63") (name "ENC_PUL_OUT_B_HI_2") (class "Default")
      (node (ref "J4") (pin "35") (pinfunction "35_35") (pintype "passive"))
      (node (ref "LINE_RECEIVER3") (pin "6") (pinfunction "2A_6") (pintype "input"))
      (node (ref "R36") (pin "2") (pinfunction "2_2") (pintype "passive"))
    )
    (net (code "64") (name "ENC_PUL_OUT_B_LO_1") (class "Default")
      (node (ref "J3") (pin "36") (pinfunction "36_36") (pintype "passive"))
      (node (ref "LINE_RECEIVER1") (pin "7") (pinfunction "2B_7") (pintype "input"))
      (node (ref "R32") (pin "1") (pinfunction "1_1") (pintype "passive"))
    )
    (net (code "65") (name "ENC_PUL_OUT_B_LO_2") (class "Default")
      (node (ref "J4") (pin "36") (pinfunction "36_36") (pintype "passive"))
      (node (ref "LINE_RECEIVER3") (pin "7") (pinfunction "2B_7") (pintype "input"))
      (node (ref "R36") (pin "1") (pinfunction "1_1") (pintype "passive"))
    )
    (net (code "66") (name "ENC_PUL_OUT_C_GPIO_1") (class "Default")
      (node (ref "LEVEL_SHIFTER2") (pin "11") (pinfunction "B3_11") (pintype "bidirectional"))
      (node (ref "STM32F2") (pin "44") (pinfunction "PE13_44") (pintype "bidirectional"))
    )
    (net (code "67") (name "ENC_PUL_OUT_C_GPIO_1_5V") (class "Default")
      (node (ref "LEVEL_SHIFTER2") (pin "4") (pinfunction "A3_4") (pintype "bidirectional"))
      (node (ref "LINE_RECEIVER1") (pin "11") (pinfunction "3Y_11") (pintype "output"))
      (node (ref "R89") (pin "2") (pinfunction "2_2") (pintype "passive"))
    )
    (net (code "68") (name "ENC_PUL_OUT_C_GPIO_2") (class "Default")
      (node (ref "LEVEL_SHIFTER3") (pin "11") (pinfunction "B3_11") (pintype "bidirectional"))
      (node (ref "STM32F2") (pin "91") (pinfunction "PB5_91") (pintype "bidirectional"))
    )
    (net (code "69") (name "ENC_PUL_OUT_C_GPIO_2_5V") (class "Default")
      (node (ref "LEVEL_SHIFTER3") (pin "4") (pinfunction "A3_4") (pintype "bidirectional"))
      (node (ref "LINE_RECEIVER3") (pin "11") (pinfunction "3Y_11") (pintype "output"))
      (node (ref "R85") (pin "2") (pinfunction "2_2") (pintype "passive"))
    )
    (net (code "70") (name "ENC_PUL_OUT_C_HI_1") (class "Default")
      (node (ref "J3") (pin "19") (pinfunction "19_19") (pintype "passive"))
      (node (ref "LINE_RECEIVER1") (pin "10") (pinfunction "3A_10") (pintype "input"))
      (node (ref "R34") (pin "2") (pinfunction "2_2") (pintype "passive"))
    )
    (net (code "71") (name "ENC_PUL_OUT_C_HI_2") (class "Default")
      (node (ref "J4") (pin "19") (pinfunction "19_19") (pintype "passive"))
      (node (ref "LINE_RECEIVER3") (pin "10") (pinfunction "3A_10") (pintype "input"))
      (node (ref "R38") (pin "2") (pinfunction "2_2") (pintype "passive"))
    )
    (net (code "72") (name "ENC_PUL_OUT_C_LO_1") (class "Default")
      (node (ref "J3") (pin "20") (pinfunction "20_20") (pintype "passive"))
      (node (ref "LINE_RECEIVER1") (pin "9") (pinfunction "3B_9") (pintype "input"))
      (node (ref "R34") (pin "1") (pinfunction "1_1") (pintype "passive"))
    )
    (net (code "73") (name "ENC_PUL_OUT_C_LO_2") (class "Default")
      (node (ref "J4") (pin "20") (pinfunction "20_20") (pintype "passive"))
      (node (ref "LINE_RECEIVER3") (pin "9") (pinfunction "3B_9") (pintype "input"))
      (node (ref "R38") (pin "1") (pinfunction "1_1") (pintype "passive"))
    )
    (net (code "74") (name "EXT_CLK") (class "Default")
      (node (ref "OSCILLATOR") (pin "2") (pinfunction "CLOCK_2") (pintype "output"))
      (node (ref "STM32F2") (pin "12") (pinfunction "PH0/OSC_IN_12") (pintype "bidirectional"))
    )
    (net (code "75") (name "EXT_IO1") (class "Default")
      (node (ref "STM32F2") (pin "51") (pinfunction "PB12_51") (pintype "bidirectional"))
    )
    (net (code "76") (name "EXT_IO2") (class "Default")
      (node (ref "STM32F2") (pin "52") (pinfunction "PB13_52") (pintype "bidirectional"))
    )
    (net (code "77") (name "EXT_IO3") (class "Default")
      (node (ref "STM32F2") (pin "57") (pinfunction "PD10_57") (pintype "bidirectional"))
    )
    (net (code "78") (name "EXT_IO4") (class "Default")
      (node (ref "STM32F2") (pin "58") (pinfunction "PD11_58") (pintype "bidirectional"))
    )
    (net (code "79") (name "EXT_IO5") (class "Default")
      (node (ref "STM32F2") (pin "60") (pinfunction "PD13_60") (pintype "bidirectional"))
    )
    (net (code "80") (name "EXT_IO6") (class "Default")
      (node (ref "STM32F2") (pin "61") (pinfunction "PD14_61") (pintype "bidirectional"))
    )
    (net (code "81") (name "EXT_IO7") (class "Default")
      (node (ref "STM32F2") (pin "62") (pinfunction "PD15_62") (pintype "bidirectional"))
    )
    (net (code "82") (name "EXT_IO8") (class "Default")
      (node (ref "STM32F2") (pin "65") (pinfunction "PC8_65") (pintype "bidirectional"))
    )
    (net (code "83") (name "EXT_IO9") (class "Default")
      (node (ref "STM32F2") (pin "66") (pinfunction "PC9_66") (pintype "bidirectional"))
    )
    (net (code "84") (name "EXT_IO10") (class "Default")
      (node (ref "STM32F2") (pin "67") (pinfunction "PA8_67") (pintype "bidirectional"))
    )
    (net (code "85") (name "EXT_IO11") (class "Default")
      (node (ref "STM32F2") (pin "68") (pinfunction "PA9_68") (pintype "bidirectional"))
    )
    (net (code "86") (name "FRWD_DRIVE_EN_AN_1") (class "Default")
      (node (ref "J3") (pin "42") (pinfunction "42_42") (pintype "passive"))
      (node (ref "NPN") (pin "12") (pinfunction "5C_12") (pintype "output"))
    )
    (net (code "87") (name "FRWD_DRIVE_EN_AN_2") (class "Default")
      (node (ref "J4") (pin "42") (pinfunction "42_42") (pintype "passive"))
      (node (ref "NPN2") (pin "14") (pinfunction "3C_14") (pintype "output"))
    )
    (net (code "88") (name "FRWD_DRIVE_EN_GPIO_1") (class "Default")
      (node (ref "NPN") (pin "5") (pinfunction "5B_5") (pintype "input"))
      (node (ref "STM32F2") (pin "36") (pinfunction "PB1_36") (pintype "bidirectional"))
    )
    (net (code "89") (name "FRWD_DRIVE_EN_GPIO_2") (class "Default")
      (node (ref "NPN2") (pin "3") (pinfunction "3B_3") (pintype "input"))
      (node (ref "STM32F2") (pin "82") (pinfunction "PD1_82") (pintype "bidirectional"))
    )
    (net (code "90") (name "FRWD_EX_TORQUE_LIM_EN_AN_1") (class "Default")
      (node (ref "J3") (pin "45") (pinfunction "45_45") (pintype "passive"))
      (node (ref "NPN") (pin "15") (pinfunction "2C_15") (pintype "output"))
    )
    (net (code "91") (name "FRWD_EX_TORQUE_LIM_EN_AN_2") (class "Default")
      (node (ref "J4") (pin "45") (pinfunction "45_45") (pintype "passive"))
      (node (ref "NPN2") (pin "11") (pinfunction "6C_11") (pintype "output"))
    )
    (net (code "92") (name "FRWD_EX_TORQUE_LIM_EN_GPIO_1") (class "Default")
      (node (ref "NPN") (pin "2") (pinfunction "2B_2") (pintype "input"))
      (node (ref "STM32F2") (pin "39") (pinfunction "PE8_39") (pintype "bidirectional"))
    )
    (net (code "93") (name "FRWD_EX_TORQUE_LIM_EN_GPIO_2") (class "Default")
      (node (ref "NPN2") (pin "6") (pinfunction "6B_6") (pintype "input"))
      (node (ref "STM32F2") (pin "85") (pinfunction "PD4_85") (pintype "bidirectional"))
    )
    (net (code "94") (name "GEN_PURPOSE_OUT_GPIO_A_1") (class "Default")
      (node (ref "LEVEL_SHIFTER1") (pin "13") (pinfunction "B1_13") (pintype "bidirectional"))
      (node (ref "STM32F2") (pin "46") (pinfunction "PE15_46") (pintype "bidirectional"))
    )
    (net (code "95") (name "GEN_PURPOSE_OUT_GPIO_A_1_5V") (class "Default")
      (node (ref "LEVEL_SHIFTER1") (pin "2") (pinfunction "A1_2") (pintype "bidirectional"))
      (node (ref "LINE_RECEIVER2") (pin "3") (pinfunction "1Y_3") (pintype "output"))
      (node (ref "R81") (pin "2") (pinfunction "2_2") (pintype "passive"))
    )
    (net (code "96") (name "GEN_PURPOSE_OUT_GPIO_A_2") (class "Default")
      (node (ref "LEVEL_SHIFTER4") (pin "13") (pinfunction "B1_13") (pintype "bidirectional"))
      (node (ref "STM32F2") (pin "93") (pinfunction "PB7_93") (pintype "bidirectional"))
    )
    (net (code "97") (name "GEN_PURPOSE_OUT_GPIO_A_2_5V") (class "Default")
      (node (ref "LEVEL_SHIFTER4") (pin "2") (pinfunction "A1_2") (pintype "bidirectional"))
      (node (ref "LINE_RECEIVER4") (pin "3") (pinfunction "1Y_3") (pintype "output"))
      (node (ref "R84") (pin "2") (pinfunction "2_2") (pintype "passive"))
    )
    (net (code "98") (name "GEN_PURPOSE_OUT_GPIO_B_1") (class "Default")
      (node (ref "LEVEL_SHIFTER1") (pin "12") (pinfunction "B2_12") (pintype "bidirectional"))
      (node (ref "STM32F2") (pin "47") (pinfunction "PB10_47") (pintype "bidirectional"))
    )
    (net (code "99") (name "GEN_PURPOSE_OUT_GPIO_B_1_5V") (class "Default")
      (node (ref "LEVEL_SHIFTER1") (pin "3") (pinfunction "A2_3") (pintype "bidirectional"))
      (node (ref "LINE_RECEIVER2") (pin "5") (pinfunction "2Y_5") (pintype "output"))
      (node (ref "R80") (pin "2") (pinfunction "2_2") (pintype "passive"))
    )
    (net (code "100") (name "GEN_PURPOSE_OUT_GPIO_B_2") (class "Default")
      (node (ref "LEVEL_SHIFTER4") (pin "12") (pinfunction "B2_12") (pintype "bidirectional"))
      (node (ref "STM32F2") (pin "95") (pinfunction "PB8_95") (pintype "bidirectional"))
    )
    (net (code "101") (name "GEN_PURPOSE_OUT_GPIO_B_2_5V") (class "Default")
      (node (ref "LEVEL_SHIFTER4") (pin "3") (pinfunction "A2_3") (pintype "bidirectional"))
      (node (ref "LINE_RECEIVER4") (pin "5") (pinfunction "2Y_5") (pintype "output"))
      (node (ref "R83") (pin "2") (pinfunction "2_2") (pintype "passive"))
    )
    (net (code "102") (name "GEN_PURPOSE_OUT_GPIO_C_1") (class "Default")
      (node (ref "LEVEL_SHIFTER1") (pin "11") (pinfunction "B3_11") (pintype "bidirectional"))
      (node (ref "STM32F2") (pin "48") (pinfunction "PB11_48") (pintype "bidirectional"))
    )
    (net (code "103") (name "GEN_PURPOSE_OUT_GPIO_C_1_5V") (class "Default")
      (node (ref "LEVEL_SHIFTER1") (pin "4") (pinfunction "A3_4") (pintype "bidirectional"))
      (node (ref "LINE_RECEIVER2") (pin "11") (pinfunction "3Y_11") (pintype "output"))
      (node (ref "R79") (pin "2") (pinfunction "2_2") (pintype "passive"))
    )
    (net (code "104") (name "GEN_PURPOSE_OUT_GPIO_C_2") (class "Default")
      (node (ref "LEVEL_SHIFTER4") (pin "11") (pinfunction "B3_11") (pintype "bidirectional"))
      (node (ref "STM32F2") (pin "96") (pinfunction "PB9_96") (pintype "bidirectional"))
    )
    (net (code "105") (name "GEN_PURPOSE_OUT_GPIO_C_2_5V") (class "Default")
      (node (ref "LEVEL_SHIFTER4") (pin "4") (pinfunction "A3_4") (pintype "bidirectional"))
      (node (ref "LINE_RECEIVER4") (pin "11") (pinfunction "3Y_11") (pintype "output"))
      (node (ref "R82") (pin "2") (pinfunction "2_2") (pintype "passive"))
    )
    (net (code "106") (name "GEN_PURPOSE_OUT_HI_A_1") (class "Default")
      (node (ref "J3") (pin "25") (pinfunction "25_25") (pintype "passive"))
      (node (ref "LINE_RECEIVER2") (pin "2") (pinfunction "1A_2") (pintype "input"))
      (node (ref "R39") (pin "1") (pinfunction "1_1") (pintype "passive"))
    )
    (net (code "107") (name "GEN_PURPOSE_OUT_HI_A_2") (class "Default")
      (node (ref "J4") (pin "25") (pinfunction "25_25") (pintype "passive"))
      (node (ref "LINE_RECEIVER4") (pin "2") (pinfunction "1A_2") (pintype "input"))
      (node (ref "R51") (pin "1") (pinfunction "1_1") (pintype "passive"))
    )
    (net (code "108") (name "GEN_PURPOSE_OUT_HI_B_1") (class "Default")
      (node (ref "J3") (pin "27") (pinfunction "27_27") (pintype "passive"))
      (node (ref "LINE_RECEIVER2") (pin "6") (pinfunction "2A_6") (pintype "input"))
      (node (ref "R42") (pin "1") (pinfunction "1_1") (pintype "passive"))
    )
    (net (code "109") (name "GEN_PURPOSE_OUT_HI_B_2") (class "Default")
      (node (ref "J4") (pin "27") (pinfunction "27_27") (pintype "passive"))
      (node (ref "LINE_RECEIVER4") (pin "6") (pinfunction "2A_6") (pintype "input"))
      (node (ref "R54") (pin "1") (pinfunction "1_1") (pintype "passive"))
    )
    (net (code "110") (name "GEN_PURPOSE_OUT_HI_C_1") (class "Default")
      (node (ref "J3") (pin "29") (pinfunction "29_29") (pintype "passive"))
      (node (ref "LINE_RECEIVER2") (pin "10") (pinfunction "3A_10") (pintype "input"))
      (node (ref "R45") (pin "1") (pinfunction "1_1") (pintype "passive"))
    )
    (net (code "111") (name "GEN_PURPOSE_OUT_HI_C_2") (class "Default")
      (node (ref "J4") (pin "29") (pinfunction "29_29") (pintype "passive"))
      (node (ref "LINE_RECEIVER4") (pin "10") (pinfunction "3A_10") (pintype "input"))
      (node (ref "R57") (pin "1") (pinfunction "1_1") (pintype "passive"))
    )
    (net (code "112") (name "GEN_PURPOSE_OUT_LO_A_1") (class "Default")
      (node (ref "C50") (pin "2") (pinfunction "2_2") (pintype "passive"))
      (node (ref "J3") (pin "26") (pinfunction "26_26") (pintype "passive"))
      (node (ref "LINE_RECEIVER2") (pin "1") (pinfunction "1B_1") (pintype "input"))
      (node (ref "R40") (pin "1") (pinfunction "1_1") (pintype "passive"))
      (node (ref "R41") (pin "2") (pinfunction "2_2") (pintype "passive"))
    )
    (net (code "113") (name "GEN_PURPOSE_OUT_LO_A_2") (class "Default")
      (node (ref "C55") (pin "2") (pinfunction "2_2") (pintype "passive"))
      (node (ref "J4") (pin "26") (pinfunction "26_26") (pintype "passive"))
      (node (ref "LINE_RECEIVER4") (pin "1") (pinfunction "1B_1") (pintype "input"))
      (node (ref "R52") (pin "1") (pinfunction "1_1") (pintype "passive"))
      (node (ref "R53") (pin "2") (pinfunction "2_2") (pintype "passive"))
    )
    (net (code "114") (name "GEN_PURPOSE_OUT_LO_B_1") (class "Default")
      (node (ref "C51") (pin "2") (pinfunction "2_2") (pintype "passive"))
      (node (ref "J3") (pin "28") (pinfunction "28_28") (pintype "passive"))
      (node (ref "LINE_RECEIVER2") (pin "7") (pinfunction "2B_7") (pintype "input"))
      (node (ref "R43") (pin "1") (pinfunction "1_1") (pintype "passive"))
      (node (ref "R44") (pin "2") (pinfunction "2_2") (pintype "passive"))
    )
    (net (code "115") (name "GEN_PURPOSE_OUT_LO_B_2") (class "Default")
      (node (ref "C56") (pin "2") (pinfunction "2_2") (pintype "passive"))
      (node (ref "J4") (pin "28") (pinfunction "28_28") (pintype "passive"))
      (node (ref "LINE_RECEIVER4") (pin "7") (pinfunction "2B_7") (pintype "input"))
      (node (ref "R55") (pin "1") (pinfunction "1_1") (pintype "passive"))
      (node (ref "R56") (pin "2") (pinfunction "2_2") (pintype "passive"))
    )
    (net (code "116") (name "GEN_PURPOSE_OUT_LO_C_1") (class "Default")
      (node (ref "C52") (pin "2") (pinfunction "2_2") (pintype "passive"))
      (node (ref "J3") (pin "30") (pinfunction "30_30") (pintype "passive"))
      (node (ref "LINE_RECEIVER2") (pin "9") (pinfunction "3B_9") (pintype "input"))
      (node (ref "R46") (pin "1") (pinfunction "1_1") (pintype "passive"))
      (node (ref "R47") (pin "2") (pinfunction "2_2") (pintype "passive"))
    )
    (net (code "117") (name "GEN_PURPOSE_OUT_LO_C_2") (class "Default")
      (node (ref "C57") (pin "2") (pinfunction "2_2") (pintype "passive"))
      (node (ref "J4") (pin "30") (pinfunction "30_30") (pintype "passive"))
      (node (ref "LINE_RECEIVER4") (pin "9") (pinfunction "3B_9") (pintype "input"))
      (node (ref "R58") (pin "1") (pinfunction "1_1") (pintype "passive"))
      (node (ref "R59") (pin "2") (pinfunction "2_2") (pintype "passive"))
    )
    (net (code "118") (name "INDIC_LED") (class "Default")
      (node (ref "R78") (pin "1") (pinfunction "1_1") (pintype "passive"))
      (node (ref "STM32F2") (pin "4") (pinfunction "PE5_4") (pintype "bidirectional"))
    )
    (net (code "119") (name "NRST") (class "Default")
      (node (ref "BUTTON") (pin "1") (pinfunction "1_1") (pintype "passive"))
      (node (ref "BUTTON") (pin "2") (pinfunction "2_2") (pintype "passive"))
      (node (ref "C62") (pin "2") (pinfunction "2_2") (pintype "passive"))
      (node (ref "R69") (pin "1") (pinfunction "1_1") (pintype "passive"))
      (node (ref "ST-LINK_CONNECTOR") (pin "1") (pinfunction "1_1") (pintype "passive"))
      (node (ref "STM32F2") (pin "14") (pinfunction "NRST_14") (pintype "bidirectional"))
    )
    (net (code "120") (name "Net-(-15V-CBOOT)") (class "Default")
      (node (ref "-15V") (pin "3") (pinfunction "CBOOT_3") (pintype "passive"))
      (node (ref "C11") (pin "2") (pinfunction "2_2") (pintype "passive"))
    )
    (net (code "121") (name "Net-(-15V-FB)") (class "Default")
      (node (ref "-15V") (pin "9") (pinfunction "FB_9") (pintype "input"))
      (node (ref "C13") (pin "1") (pinfunction "1_1") (pintype "passive"))
      (node (ref "R4") (pin "2") (pinfunction "2_2") (pintype "passive"))
      (node (ref "R5") (pin "1") (pinfunction "1_1") (pintype "passive"))
    )
    (net (code "122") (name "Net-(-15V-PGOOD)") (class "Default")
      (node (ref "-15V") (pin "8") (pinfunction "PGOOD_8") (pintype "output"))
      (node (ref "R3") (pin "2") (pinfunction "2_2") (pintype "passive"))
    )
    (net (code "123") (name "Net-(-15V-VCC)") (class "Default")
      (node (ref "-15V") (pin "4") (pinfunction "VCC_4") (pintype "power_in"))
      (node (ref "C10") (pin "2") (pinfunction "2_2") (pintype "passive"))
    )
    (net (code "124") (name "Net-(5V-CB)") (class "Default")
      (node (ref "0.01UF_C7") (pin "1") (pinfunction "1_1") (pintype "passive"))
      (node (ref "5V") (pin "3") (pinfunction "CB_3") (pintype "passive"))
    )
    (net (code "125") (name "Net-(LED1-PadA)") (class "Default")
      (node (ref "LED1") (pin "A") (pinfunction "A_A") (pintype "passive"))
      (node (ref "R19") (pin "2") (pinfunction "2_2") (pintype "passive"))
    )
    (net (code "126") (name "Net-(LED2-PadA)") (class "Default")
      (node (ref "LED2") (pin "A") (pinfunction "A_A") (pintype "passive"))
      (node (ref "R20") (pin "2") (pinfunction "2_2") (pintype "passive"))
    )
    (net (code "127") (name "Net-(LED3-PadA)") (class "Default")
      (node (ref "LED3") (pin "A") (pinfunction "A_A") (pintype "passive"))
      (node (ref "R21") (pin "2") (pinfunction "2_2") (pintype "passive"))
    )
    (net (code "128") (name "Net-(LED4-PadA)") (class "Default")
      (node (ref "LED4") (pin "A") (pinfunction "A_A") (pintype "passive"))
      (node (ref "R22") (pin "2") (pinfunction "2_2") (pintype "passive"))
    )
    (net (code "129") (name "Net-(LED5-PadA)") (class "Default")
      (node (ref "LED5") (pin "A") (pinfunction "A_A") (pintype "passive"))
      (node (ref "R50") (pin "2") (pinfunction "2_2") (pintype "passive"))
    )
    (net (code "130") (name "Net-(LED6-PadA)") (class "Default")
      (node (ref "LED6") (pin "A") (pinfunction "A_A") (pintype "passive"))
      (node (ref "R60") (pin "2") (pinfunction "2_2") (pintype "passive"))
    )
    (net (code "131") (name "Net-(LED7-PadA)") (class "Default")
      (node (ref "LED7") (pin "A") (pinfunction "A_A") (pintype "passive"))
      (node (ref "R61") (pin "2") (pinfunction "2_2") (pintype "passive"))
    )
    (net (code "132") (name "Net-(LED8-PadA)") (class "Default")
      (node (ref "LED8") (pin "A") (pinfunction "A_A") (pintype "passive"))
      (node (ref "R62") (pin "2") (pinfunction "2_2") (pintype "passive"))
    )
    (net (code "133") (name "Net-(LED9-PadA)") (class "Default")
      (node (ref "LED9") (pin "A") (pinfunction "A_A") (pintype "passive"))
      (node (ref "R77") (pin "2") (pinfunction "2_2") (pintype "passive"))
    )
    (net (code "134") (name "Net-(LED10-PadA)") (class "Default")
      (node (ref "LED10") (pin "A") (pinfunction "A_A") (pintype "passive"))
      (node (ref "R78") (pin "2") (pinfunction "2_2") (pintype "passive"))
    )
    (net (code "135") (name "Net-(OPTOCOUPLER-ANODE1)") (class "Default")
      (node (ref "D1") (pin "C") (pinfunction "C_C") (pintype "passive"))
      (node (ref "OPTOCOUPLER") (pin "1") (pinfunction "ANODE1_1") (pintype "bidirectional"))
      (node (ref "R17") (pin "1") (pinfunction "1_1") (pintype "passive"))
    )
    (net (code "136") (name "Net-(OPTOCOUPLER-ANODE2)") (class "Default")
      (node (ref "D2") (pin "C") (pinfunction "C_C") (pintype "passive"))
      (node (ref "OPTOCOUPLER") (pin "3") (pinfunction "ANODE2_3") (pintype "bidirectional"))
      (node (ref "R18") (pin "1") (pinfunction "1_1") (pintype "passive"))
    )
    (net (code "137") (name "Net-(OPTOCOUPLER-ANODE3)") (class "Default")
      (node (ref "D3") (pin "C") (pinfunction "C_C") (pintype "passive"))
      (node (ref "OPTOCOUPLER") (pin "5") (pinfunction "ANODE3_5") (pintype "bidirectional"))
      (node (ref "R27") (pin "1") (pinfunction "1_1") (pintype "passive"))
    )
    (net (code "138") (name "Net-(OPTOCOUPLER-ANODE4)") (class "Default")
      (node (ref "D7") (pin "C") (pinfunction "C_C") (pintype "passive"))
      (node (ref "OPTOCOUPLER") (pin "7") (pinfunction "ANODE4_7") (pintype "bidirectional"))
      (node (ref "R48") (pin "1") (pinfunction "1_1") (pintype "passive"))
    )
    (net (code "139") (name "Net-(OPTOCOUPLER2-ANODE1)") (class "Default")
      (node (ref "D4") (pin "C") (pinfunction "C_C") (pintype "passive"))
      (node (ref "OPTOCOUPLER2") (pin "1") (pinfunction "ANODE1_1") (pintype "bidirectional"))
      (node (ref "R28") (pin "1") (pinfunction "1_1") (pintype "passive"))
    )
    (net (code "140") (name "Net-(OPTOCOUPLER2-ANODE2)") (class "Default")
      (node (ref "D5") (pin "C") (pinfunction "C_C") (pintype "passive"))
      (node (ref "OPTOCOUPLER2") (pin "3") (pinfunction "ANODE2_3") (pintype "bidirectional"))
      (node (ref "R29") (pin "1") (pinfunction "1_1") (pintype "passive"))
    )
    (net (code "141") (name "Net-(OPTOCOUPLER2-ANODE3)") (class "Default")
      (node (ref "D6") (pin "C") (pinfunction "C_C") (pintype "passive"))
      (node (ref "OPTOCOUPLER2") (pin "5") (pinfunction "ANODE3_5") (pintype "bidirectional"))
      (node (ref "R30") (pin "1") (pinfunction "1_1") (pintype "passive"))
    )
    (net (code "142") (name "Net-(OP_AMP-+IN_2)") (class "Default")
      (node (ref "OP_AMP") (pin "5") (pinfunction "+IN_2_5") (pintype "output"))
      (node (ref "R11") (pin "2") (pinfunction "2_2") (pintype "passive"))
      (node (ref "R12") (pin "2") (pinfunction "2_2") (pintype "passive"))
    )
    (net (code "143") (name "Net-(OP_AMP-+IN_4)") (class "Default")
      (node (ref "OP_AMP") (pin "12") (pinfunction "+IN_4_12") (pintype "output"))
      (node (ref "R15") (pin "2") (pinfunction "2_2") (pintype "passive"))
      (node (ref "R16") (pin "2") (pinfunction "2_2") (pintype "passive"))
    )
    (net (code "144") (name "Net-(OP_AMP--IN_2)") (class "Default")
      (node (ref "OP_AMP") (pin "6") (pinfunction "-IN_2_6") (pintype "output"))
      (node (ref "R10") (pin "2") (pinfunction "2_2") (pintype "passive"))
      (node (ref "R9") (pin "2") (pinfunction "2_2") (pintype "passive"))
    )
    (net (code "145") (name "Net-(OP_AMP--IN_4)") (class "Default")
      (node (ref "OP_AMP") (pin "13") (pinfunction "-IN_4_13") (pintype "output"))
      (node (ref "R13") (pin "2") (pinfunction "2_2") (pintype "passive"))
      (node (ref "R14") (pin "2") (pinfunction "2_2") (pintype "passive"))
    )
    (net (code "146") (name "Net-(R7-Pad3)") (class "Default")
      (node (ref "R7") (pin "3") (pinfunction "3_3") (pintype "passive"))
      (node (ref "R8") (pin "1") (pinfunction "1_1") (pintype "passive"))
    )
    (net (code "147") (name "Net-(STM32F2C-VCAP_1)") (class "Default")
      (node (ref "C35") (pin "2") (pinfunction "2_2") (pintype "passive"))
      (node (ref "STM32F2") (pin "49") (pinfunction "VCAP_1_49") (pintype "power_in"))
    )
    (net (code "148") (name "Net-(STM32F2C-VCAP_2)") (class "Default")
      (node (ref "C34") (pin "2") (pinfunction "2_2") (pintype "passive"))
      (node (ref "STM32F2") (pin "73") (pinfunction "VCAP_2_73") (pintype "power_in"))
    )
    (net (code "149") (name "POS_CON_LED") (class "Default")
      (node (ref "R60") (pin "1") (pinfunction "1_1") (pintype "passive"))
      (node (ref "STM32F2") (pin "98") (pinfunction "PE1_98") (pintype "bidirectional"))
    )
    (net (code "150") (name "POS_EN_GPIO") (class "Default")
      (node (ref "LINE_DRIVER1") (pin "5") (pinfunction "1/2EN_5") (pintype "passive"))
      (node (ref "LINE_DRIVER2") (pin "5") (pinfunction "1/2EN_5") (pintype "passive"))
      (node (ref "STM32F2") (pin "56") (pinfunction "PD9_56") (pintype "bidirectional"))
    )
    (net (code "151") (name "PROP_CONTROL_EN_AN_1") (class "Default")
      (node (ref "J3") (pin "41") (pinfunction "41_41") (pintype "passive"))
      (node (ref "NPN") (pin "11") (pinfunction "6C_11") (pintype "output"))
    )
    (net (code "152") (name "PROP_CONTROL_EN_AN_2") (class "Default")
      (node (ref "J4") (pin "41") (pinfunction "41_41") (pintype "passive"))
      (node (ref "NPN2") (pin "15") (pinfunction "2C_15") (pintype "output"))
    )
    (net (code "153") (name "PROP_CONTROL_EN_GPIO_1") (class "Default")
      (node (ref "NPN") (pin "6") (pinfunction "6B_6") (pintype "input"))
      (node (ref "STM32F2") (pin "35") (pinfunction "PB0_35") (pintype "bidirectional"))
    )
    (net (code "154") (name "PROP_CONTROL_EN_GPIO_2") (class "Default")
      (node (ref "NPN2") (pin "2") (pinfunction "2B_2") (pintype "input"))
      (node (ref "STM32F2") (pin "81") (pinfunction "PD0_81") (pintype "bidirectional"))
    )
    (net (code "155") (name "PULSE_GPIO_1") (class "Default")
      (node (ref "LINE_DRIVER1") (pin "1") (pinfunction "1A_1") (pintype "input"))
      (node (ref "STM32F2") (pin "53") (pinfunction "PB14_53") (pintype "bidirectional"))
    )
    (net (code "156") (name "PULSE_GPIO_2") (class "Default")
      (node (ref "LINE_DRIVER2") (pin "1") (pinfunction "1A_1") (pintype "input"))
      (node (ref "STM32F2") (pin "70") (pinfunction "PA11_70") (pintype "bidirectional"))
    )
    (net (code "157") (name "PULSE_HI_1") (class "Default")
      (node (ref "J3") (pin "7") (pinfunction "7_7") (pintype "passive"))
      (node (ref "LINE_DRIVER1") (pin "2") (pinfunction "1Y_2") (pintype "output"))
    )
    (net (code "158") (name "PULSE_HI_2") (class "Default")
      (node (ref "J4") (pin "7") (pinfunction "7_7") (pintype "passive"))
      (node (ref "LINE_DRIVER2") (pin "2") (pinfunction "1Y_2") (pintype "output"))
    )
    (net (code "159") (name "PULSE_LO_1") (class "Default")
      (node (ref "J3") (pin "8") (pinfunction "8_8") (pintype "passive"))
      (node (ref "LINE_DRIVER1") (pin "4") (pinfunction "1Z_4") (pintype "output"))
    )
    (net (code "160") (name "PULSE_LO_2") (class "Default")
      (node (ref "J4") (pin "8") (pinfunction "8_8") (pintype "passive"))
      (node (ref "LINE_DRIVER2") (pin "4") (pinfunction "1Z_4") (pintype "output"))
    )
    (net (code "161") (name "P_GND") (class "Default")
      (node (ref "-15V") (pin "5") (pinfunction "BIAS_5") (pintype "input"))
      (node (ref "14_JACK") (pin "2") (pinfunction "2_2") (pintype "passive"))
      (node (ref "14_JACK") (pin "3") (pinfunction "3_3") (pintype "passive"))
      (node (ref "180UF") (pin "2") (pinfunction "2_2") (pintype "passive"))
      (node (ref "330UF_C3") (pin "2") (pinfunction "2_2") (pintype "passive"))
      (node (ref "5V") (pin "4") (pinfunction "GND_4") (pintype "passive"))
      (node (ref "5V") (pin "8") (pinfunction "TAB_8") (pintype "passive"))
      (node (ref "C1") (pin "1") (pinfunction "1_1") (pintype "passive"))
      (node (ref "C12") (pin "2") (pinfunction "2_2") (pintype "passive"))
      (node (ref "C13") (pin "2") (pinfunction "2_2") (pintype "passive"))
      (node (ref "C14") (pin "2") (pinfunction "2_2") (pintype "passive"))
      (node (ref "C5") (pin "2") (pinfunction "2_2") (pintype "passive"))
      (node (ref "C6") (pin "2") (pinfunction "2_2") (pintype "passive"))
      (node (ref "C8") (pin "2") (pinfunction "2_2") (pintype "passive"))
      (node (ref "DIODE") (pin "2") (pinfunction "2_2") (pintype "passive"))
      (node (ref "J1") (pin "2") (pinfunction "2_2") (pintype "passive"))
      (node (ref "J1") (pin "3") (pinfunction "3_3") (pintype "passive"))
      (node (ref "J3") (pin "1") (pinfunction "1_1") (pintype "passive"))
      (node (ref "J3") (pin "10") (pinfunction "10_10") (pintype "passive"))
      (node (ref "J3") (pin "6") (pinfunction "6_6") (pintype "passive"))
      (node (ref "J4") (pin "1") (pinfunction "1_1") (pintype "passive"))
      (node (ref "J4") (pin "10") (pinfunction "10_10") (pintype "passive"))
      (node (ref "J4") (pin "32") (pinfunction "32_32") (pintype "passive"))
      (node (ref "J4") (pin "6") (pinfunction "6_6") (pintype "passive"))
      (node (ref "L3") (pin "1") (pinfunction "1_1") (pintype "passive"))
      (node (ref "L4") (pin "2") (pinfunction "2_2") (pintype "passive"))
      (node (ref "LDO") (pin "1") (pinfunction "GND_1") (pintype "power_in"))
      (node (ref "LED1") (pin "C") (pinfunction "C_C") (pintype "passive"))
      (node (ref "LED10") (pin "C") (pinfunction "C_C") (pintype "passive"))
      (node (ref "LED3") (pin "C") (pinfunction "C_C") (pintype "passive"))
      (node (ref "LED4") (pin "C") (pinfunction "C_C") (pintype "passive"))
      (node (ref "LED5") (pin "C") (pinfunction "C_C") (pintype "passive"))
      (node (ref "LED6") (pin "C") (pinfunction "C_C") (pintype "passive"))
      (node (ref "LED7") (pin "C") (pinfunction "C_C") (pintype "passive"))
      (node (ref "LED8") (pin "C") (pinfunction "C_C") (pintype "passive"))
      (node (ref "LED9") (pin "C") (pinfunction "C_C") (pintype "passive"))
      (node (ref "NPN") (pin "8") (pinfunction "E_8") (pintype "power_in"))
      (node (ref "NPN2") (pin "8") (pinfunction "E_8") (pintype "power_in"))
      (node (ref "R1") (pin "1") (pinfunction "1_1") (pintype "passive"))
      (node (ref "R10") (pin "1") (pinfunction "1_1") (pintype "passive"))
      (node (ref "R14") (pin "1") (pinfunction "1_1") (pintype "passive"))
      (node (ref "R20") (pin "1") (pinfunction "1_1") (pintype "passive"))
      (node (ref "R3") (pin "1") (pinfunction "1_1") (pintype "passive"))
      (node (ref "R5") (pin "2") (pinfunction "2_2") (pintype "passive"))
      (node (ref "R7") (pin "1") (pinfunction "1_1") (pintype "passive"))
      (node (ref "TP5") (pin "1") (pinfunction "1_1") (pintype "bidirectional"))
    )
    (net (code "162") (name "REVERSE_DRIVE_EN_AN_1") (class "Default")
      (node (ref "J3") (pin "43") (pinfunction "43_43") (pintype "passive"))
      (node (ref "NPN") (pin "13") (pinfunction "4C_13") (pintype "output"))
    )
    (net (code "163") (name "REVERSE_DRIVE_EN_AN_2") (class "Default")
      (node (ref "J4") (pin "43") (pinfunction "43_43") (pintype "passive"))
      (node (ref "NPN2") (pin "13") (pinfunction "4C_13") (pintype "output"))
    )
    (net (code "164") (name "REVERSE_DRIVE_EN_GPIO_1") (class "Default")
      (node (ref "NPN") (pin "4") (pinfunction "4B_4") (pintype "input"))
      (node (ref "STM32F2") (pin "37") (pinfunction "PB2_37") (pintype "bidirectional"))
    )
    (net (code "165") (name "REVERSE_DRIVE_EN_GPIO_2") (class "Default")
      (node (ref "NPN2") (pin "4") (pinfunction "4B_4") (pintype "input"))
      (node (ref "STM32F2") (pin "83") (pinfunction "PD2_83") (pintype "bidirectional"))
    )
    (net (code "166") (name "REVERSE_EX_TORQUE_LIM_EN_AN_1") (class "Default")
      (node (ref "J3") (pin "46") (pinfunction "46_46") (pintype "passive"))
      (node (ref "NPN") (pin "16") (pinfunction "1C_16") (pintype "output"))
    )
    (net (code "167") (name "REVERSE_EX_TORQUE_LIM_EN_AN_2") (class "Default")
      (node (ref "J4") (pin "46") (pinfunction "46_46") (pintype "passive"))
      (node (ref "NPN2") (pin "10") (pinfunction "7C_10") (pintype "output"))
    )
    (net (code "168") (name "REVERSE_EX_TORQUE_LIM_EN_GPIO_1") (class "Default")
      (node (ref "NPN") (pin "1") (pinfunction "1B_1") (pintype "input"))
      (node (ref "STM32F2") (pin "40") (pinfunction "PE9_40") (pintype "bidirectional"))
    )
    (net (code "169") (name "REVERSE_EX_TORQUE_LIM_EN_GPIO_2") (class "Default")
      (node (ref "NPN2") (pin "7") (pinfunction "7B_7") (pintype "input"))
      (node (ref "STM32F2") (pin "86") (pinfunction "PD5_86") (pintype "bidirectional"))
    )
    (net (code "170") (name "SERVO_ALARM_AN_1") (class "Default")
      (node (ref "D7") (pin "A") (pinfunction "A_A") (pintype "passive"))
      (node (ref "J3") (pin "31") (pinfunction "31_31") (pintype "passive"))
      (node (ref "OPTOCOUPLER") (pin "8") (pinfunction "CATHODE4_8") (pintype "bidirectional"))
    )
    (net (code "171") (name "SERVO_ALARM_AN_2") (class "Default")
      (node (ref "J3") (pin "32") (pinfunction "32_32") (pintype "passive"))
      (node (ref "J4") (pin "31") (pinfunction "31_31") (pintype "passive"))
    )
    (net (code "172") (name "SERVO_ALARM_GPIO") (class "Default")
      (node (ref "OPTOCOUPLER") (pin "11") (pinfunction "V04_11") (pintype "bidirectional"))
      (node (ref "R49") (pin "1") (pinfunction "1_1") (pintype "passive"))
      (node (ref "STM32F2") (pin "25") (pinfunction "PA2_25") (pintype "bidirectional"))
    )
    (net (code "173") (name "SERVO_EN_AN_1") (class "Default")
      (node (ref "J3") (pin "40") (pinfunction "40_40") (pintype "passive"))
      (node (ref "NPN") (pin "10") (pinfunction "7C_10") (pintype "output"))
    )
    (net (code "174") (name "SERVO_EN_AN_2") (class "Default")
      (node (ref "J4") (pin "40") (pinfunction "40_40") (pintype "passive"))
      (node (ref "NPN2") (pin "16") (pinfunction "1C_16") (pintype "output"))
    )
    (net (code "175") (name "SERVO_EN_GPIO_1") (class "Default")
      (node (ref "NPN") (pin "7") (pinfunction "7B_7") (pintype "input"))
      (node (ref "STM32F2") (pin "34") (pinfunction "PC5_34") (pintype "bidirectional"))
    )
    (net (code "176") (name "SERVO_EN_GPIO_2") (class "Default")
      (node (ref "NPN2") (pin "1") (pinfunction "1B_1") (pintype "input"))
      (node (ref "STM32F2") (pin "80") (pinfunction "PC12_80") (pintype "bidirectional"))
    )
    (net (code "177") (name "SWCLK") (class "Default")
      (node (ref "ST-LINK_CONNECTOR") (pin "6") (pinfunction "6_6") (pintype "passive"))
      (node (ref "STM32F2") (pin "76") (pinfunction "PA14_76") (pintype "bidirectional"))
    )
    (net (code "178") (name "SWDIO") (class "Default")
      (node (ref "ST-LINK_CONNECTOR") (pin "2") (pinfunction "2_2") (pintype "passive"))
      (node (ref "STM32F2") (pin "72") (pinfunction "PA13_72") (pintype "bidirectional"))
    )
    (net (code "179") (name "SWITCH_OUT_5V") (class "Default")
      (node (ref "0.01UF_C7") (pin "2") (pinfunction "2_2") (pintype "passive"))
      (node (ref "10UH_L1") (pin "1") (pinfunction "1_1") (pintype "passive"))
      (node (ref "5V") (pin "1") (pinfunction "VSW_1") (pintype "output"))
      (node (ref "DIODE") (pin "1") (pinfunction "1_1") (pintype "passive"))
    )
    (net (code "180") (name "SW_OUT") (class "Default")
      (node (ref "-15V") (pin "1") (pinfunction "SW_2_1") (pintype "output"))
      (node (ref "-15V") (pin "2") (pinfunction "SW_2") (pintype "output"))
      (node (ref "C11") (pin "1") (pinfunction "1_1") (pintype "passive"))
      (node (ref "L3") (pin "2") (pinfunction "2_2") (pintype "passive"))
    )
    (net (code "181") (name "S_GND") (class "Default")
      (node (ref "BUTTON") (pin "3") (pinfunction "3_3") (pintype "passive"))
      (node (ref "BUTTON") (pin "4") (pinfunction "4_4") (pintype "passive"))
      (node (ref "C15") (pin "1") (pinfunction "1_1") (pintype "passive"))
      (node (ref "C16") (pin "1") (pinfunction "1_1") (pintype "passive"))
      (node (ref "C17") (pin "1") (pinfunction "1_1") (pintype "passive"))
      (node (ref "C18") (pin "1") (pinfunction "1_1") (pintype "passive"))
      (node (ref "C19") (pin "1") (pinfunction "1_1") (pintype "passive"))
      (node (ref "C20") (pin "1") (pinfunction "1_1") (pintype "passive"))
      (node (ref "C21") (pin "1") (pinfunction "1_1") (pintype "passive"))
      (node (ref "C22") (pin "1") (pinfunction "1_1") (pintype "passive"))
      (node (ref "C23") (pin "1") (pinfunction "1_1") (pintype "passive"))
      (node (ref "C24") (pin "1") (pinfunction "1_1") (pintype "passive"))
      (node (ref "C25") (pin "1") (pinfunction "1_1") (pintype "passive"))
      (node (ref "C26") (pin "1") (pinfunction "1_1") (pintype "passive"))
      (node (ref "C27") (pin "1") (pinfunction "1_1") (pintype "passive"))
      (node (ref "C28") (pin "1") (pinfunction "1_1") (pintype "passive"))
      (node (ref "C29") (pin "1") (pinfunction "1_1") (pintype "passive"))
      (node (ref "C30") (pin "1") (pinfunction "1_1") (pintype "passive"))
      (node (ref "C31") (pin "1") (pinfunction "1_1") (pintype "passive"))
      (node (ref "C34") (pin "1") (pinfunction "1_1") (pintype "passive"))
      (node (ref "C35") (pin "1") (pinfunction "1_1") (pintype "passive"))
      (node (ref "C36") (pin "1") (pinfunction "1_1") (pintype "passive"))
      (node (ref "C4") (pin "1") (pinfunction "1_1") (pintype "passive"))
      (node (ref "C46") (pin "1") (pinfunction "1_1") (pintype "passive"))
      (node (ref "C47") (pin "1") (pinfunction "1_1") (pintype "passive"))
      (node (ref "C48") (pin "1") (pinfunction "1_1") (pintype "passive"))
      (node (ref "C49") (pin "1") (pinfunction "1_1") (pintype "passive"))
      (node (ref "C50") (pin "1") (pinfunction "1_1") (pintype "passive"))
      (node (ref "C51") (pin "1") (pinfunction "1_1") (pintype "passive"))
      (node (ref "C52") (pin "1") (pinfunction "1_1") (pintype "passive"))
      (node (ref "C54") (pin "1") (pinfunction "1_1") (pintype "passive"))
      (node (ref "C55") (pin "1") (pinfunction "1_1") (pintype "passive"))
      (node (ref "C56") (pin "1") (pinfunction "1_1") (pintype "passive"))
      (node (ref "C57") (pin "1") (pinfunction "1_1") (pintype "passive"))
      (node (ref "C59") (pin "1") (pinfunction "1_1") (pintype "passive"))
      (node (ref "C60") (pin "1") (pinfunction "1_1") (pintype "passive"))
      (node (ref "C61") (pin "1") (pinfunction "1_1") (pintype "passive"))
      (node (ref "C62") (pin "1") (pinfunction "1_1") (pintype "passive"))
      (node (ref "L2") (pin "1") (pinfunction "1_1") (pintype "passive"))
      (node (ref "L4") (pin "1") (pinfunction "1_1") (pintype "passive"))
      (node (ref "LEVEL_SHIFTER1") (pin "7") (pinfunction "GND_7") (pintype "passive"))
      (node (ref "LEVEL_SHIFTER2") (pin "7") (pinfunction "GND_7") (pintype "passive"))
      (node (ref "LEVEL_SHIFTER3") (pin "7") (pinfunction "GND_7") (pintype "passive"))
      (node (ref "LEVEL_SHIFTER4") (pin "7") (pinfunction "GND_7") (pintype "passive"))
      (node (ref "LINE_DRIVER1") (pin "10") (pinfunction "GND_10") (pintype "power_in"))
      (node (ref "LINE_DRIVER2") (pin "10") (pinfunction "GND_10") (pintype "power_in"))
      (node (ref "LINE_RECEIVER1") (pin "8") (pinfunction "GND_8") (pintype "power_in"))
      (node (ref "LINE_RECEIVER2") (pin "8") (pinfunction "GND_8") (pintype "power_in"))
      (node (ref "LINE_RECEIVER3") (pin "8") (pinfunction "GND_8") (pintype "power_in"))
      (node (ref "LINE_RECEIVER4") (pin "8") (pinfunction "GND_8") (pintype "power_in"))
      (node (ref "OPTOCOUPLER") (pin "16") (pinfunction "GND_16") (pintype "passive"))
      (node (ref "OPTOCOUPLER") (pin "9") (pinfunction "GND_2_9") (pintype "passive"))
      (node (ref "OPTOCOUPLER2") (pin "16") (pinfunction "GND_16") (pintype "passive"))
      (node (ref "OPTOCOUPLER2") (pin "9") (pinfunction "GND_2_9") (pintype "passive"))
      (node (ref "OSCILLATOR") (pin "3") (pinfunction "GND_3") (pintype "power_in"))
      (node (ref "R23") (pin "1") (pinfunction "1_1") (pintype "passive"))
      (node (ref "R25") (pin "1") (pinfunction "1_1") (pintype "passive"))
      (node (ref "R41") (pin "1") (pinfunction "1_1") (pintype "passive"))
      (node (ref "R44") (pin "1") (pinfunction "1_1") (pintype "passive"))
      (node (ref "R47") (pin "1") (pinfunction "1_1") (pintype "passive"))
      (node (ref "R53") (pin "1") (pinfunction "1_1") (pintype "passive"))
      (node (ref "R56") (pin "1") (pinfunction "1_1") (pintype "passive"))
      (node (ref "R59") (pin "1") (pinfunction "1_1") (pintype "passive"))
      (node (ref "R70") (pin "1") (pinfunction "1_1") (pintype "passive"))
      (node (ref "R72") (pin "1") (pinfunction "1_1") (pintype "passive"))
      (node (ref "R74") (pin "1") (pinfunction "1_1") (pintype "passive"))
      (node (ref "R76") (pin "1") (pinfunction "1_1") (pintype "passive"))
      (node (ref "R79") (pin "1") (pinfunction "1_1") (pintype "passive"))
      (node (ref "R80") (pin "1") (pinfunction "1_1") (pintype "passive"))
      (node (ref "R81") (pin "1") (pinfunction "1_1") (pintype "passive"))
      (node (ref "R82") (pin "1") (pinfunction "1_1") (pintype "passive"))
      (node (ref "R83") (pin "1") (pinfunction "1_1") (pintype "passive"))
      (node (ref "R84") (pin "1") (pinfunction "1_1") (pintype "passive"))
      (node (ref "R85") (pin "1") (pinfunction "1_1") (pintype "passive"))
      (node (ref "R86") (pin "1") (pinfunction "1_1") (pintype "passive"))
      (node (ref "R87") (pin "1") (pinfunction "1_1") (pintype "passive"))
      (node (ref "R88") (pin "1") (pinfunction "1_1") (pintype "passive"))
      (node (ref "R89") (pin "1") (pinfunction "1_1") (pintype "passive"))
      (node (ref "R90") (pin "1") (pinfunction "1_1") (pintype "passive"))
      (node (ref "R91") (pin "1") (pinfunction "1_1") (pintype "passive"))
      (node (ref "R92") (pin "1") (pinfunction "1_1") (pintype "passive"))
      (node (ref "ST-LINK_CONNECTOR") (pin "3") (pinfunction "3_3") (pintype "passive"))
      (node (ref "ST-LINK_CONNECTOR") (pin "4") (pinfunction "4_4") (pintype "passive"))
      (node (ref "STM32F2") (pin "10") (pinfunction "VSS_2_10") (pintype "power_in"))
      (node (ref "STM32F2") (pin "27") (pinfunction "VSS_3_27") (pintype "power_in"))
      (node (ref "STM32F2") (pin "74") (pinfunction "VSS_74") (pintype "power_in"))
      (node (ref "STM32F2") (pin "94") (pinfunction "BOOT0_94") (pintype "input"))
      (node (ref "TP6") (pin "1") (pinfunction "1_1") (pintype "bidirectional"))
      (node (ref "UART_CONNECTOR") (pin "01") (pinfunction "01_01") (pintype "passive"))
      (node (ref "UART_CONNECTOR") (pin "02") (pinfunction "02_02") (pintype "passive"))
    )
    (net (code "182") (name "S_GNDA") (class "Default")
      (node (ref "C32") (pin "1") (pinfunction "1_1") (pintype "passive"))
      (node (ref "C33") (pin "1") (pinfunction "1_1") (pintype "passive"))
      (node (ref "L2") (pin "2") (pinfunction "2_2") (pintype "passive"))
      (node (ref "STM32F2") (pin "20") (pinfunction "VSSA_20") (pintype "power_in"))
    )
    (net (code "183") (name "TORQUE-SPEED_ANALOG_1") (class "Default")
      (node (ref "J3") (pin "5") (pinfunction "5_5") (pintype "passive"))
      (node (ref "J3") (pin "9") (pinfunction "9_9") (pintype "passive"))
      (node (ref "OP_AMP") (pin "7") (pinfunction "OUT_2_7") (pintype "output"))
      (node (ref "R12") (pin "1") (pinfunction "1_1") (pintype "passive"))
    )
    (net (code "184") (name "TORQUE-SPEED_ANALOG_2") (class "Default")
      (node (ref "J4") (pin "5") (pinfunction "5_5") (pintype "passive"))
      (node (ref "J4") (pin "9") (pinfunction "9_9") (pintype "passive"))
      (node (ref "OP_AMP") (pin "14") (pinfunction "OUT_4_14") (pintype "output"))
      (node (ref "R15") (pin "1") (pinfunction "1_1") (pintype "passive"))
    )
    (net (code "185") (name "TORQUE-SPEED_DAC_1") (class "Default")
      (node (ref "J2") (pin "1") (pinfunction "1_1") (pintype "bidirectional"))
      (node (ref "STM32F2") (pin "29") (pinfunction "PA4_29") (pintype "bidirectional"))
    )
    (net (code "186") (name "TORQUE-SPEED_DAC_2") (class "Default")
      (node (ref "J5") (pin "1") (pinfunction "1_1") (pintype "bidirectional"))
      (node (ref "STM32F2") (pin "30") (pinfunction "PA5_30") (pintype "bidirectional"))
    )
    (net (code "187") (name "UART_LED") (class "Default")
      (node (ref "R50") (pin "1") (pinfunction "1_1") (pintype "passive"))
      (node (ref "STM32F2") (pin "97") (pinfunction "PE0_97") (pintype "bidirectional"))
    )
    (net (code "188") (name "UART_RX") (class "Default")
      (node (ref "STM32F2") (pin "64") (pinfunction "PC7_64") (pintype "bidirectional"))
      (node (ref "UART_CONNECTOR") (pin "04") (pinfunction "04_04") (pintype "passive"))
    )
    (net (code "189") (name "UART_TX") (class "Default")
      (node (ref "STM32F2") (pin "63") (pinfunction "PC6_63") (pintype "bidirectional"))
      (node (ref "UART_CONNECTOR") (pin "05") (pinfunction "05_05") (pintype "passive"))
    )
    (net (code "190") (name "V_ON_5V_1") (class "Default")
      (node (ref "LINE_RECEIVER2") (pin "12") (pinfunction "3/4EN_12") (pintype "passive"))
      (node (ref "LINE_RECEIVER2") (pin "4") (pinfunction "1/2EN_4") (pintype "passive"))
      (node (ref "R23") (pin "2") (pinfunction "2_2") (pintype "passive"))
      (node (ref "R6") (pin "1") (pinfunction "1_1") (pintype "passive"))
    )
    (net (code "191") (name "V_ON_5V_2") (class "Default")
      (node (ref "LINE_DRIVER1") (pin "15") (pinfunction "3/42N_15") (pintype "passive"))
      (node (ref "R24") (pin "1") (pinfunction "1_1") (pintype "passive"))
      (node (ref "R25") (pin "2") (pinfunction "2_2") (pintype "passive"))
    )
    (net (code "192") (name "V_ON_5V_3") (class "Default")
      (node (ref "LINE_RECEIVER1") (pin "12") (pinfunction "3/4EN_12") (pintype "passive"))
      (node (ref "LINE_RECEIVER1") (pin "4") (pinfunction "1/2EN_4") (pintype "passive"))
      (node (ref "R26") (pin "1") (pinfunction "1_1") (pintype "passive"))
      (node (ref "R70") (pin "2") (pinfunction "2_2") (pintype "passive"))
    )
    (net (code "193") (name "V_ON_5V_4") (class "Default")
      (node (ref "LINE_RECEIVER3") (pin "12") (pinfunction "3/4EN_12") (pintype "passive"))
      (node (ref "LINE_RECEIVER3") (pin "4") (pinfunction "1/2EN_4") (pintype "passive"))
      (node (ref "R71") (pin "1") (pinfunction "1_1") (pintype "passive"))
      (node (ref "R72") (pin "2") (pinfunction "2_2") (pintype "passive"))
    )
    (net (code "194") (name "V_ON_5V_5") (class "Default")
      (node (ref "LINE_RECEIVER4") (pin "12") (pinfunction "3/4EN_12") (pintype "passive"))
      (node (ref "LINE_RECEIVER4") (pin "4") (pinfunction "1/2EN_4") (pintype "passive"))
      (node (ref "R73") (pin "1") (pinfunction "1_1") (pintype "passive"))
      (node (ref "R74") (pin "2") (pinfunction "2_2") (pintype "passive"))
    )
    (net (code "195") (name "V_ON_5V_6") (class "Default")
      (node (ref "LINE_DRIVER2") (pin "15") (pinfunction "3/42N_15") (pintype "passive"))
      (node (ref "R75") (pin "1") (pinfunction "1_1") (pintype "passive"))
      (node (ref "R76") (pin "2") (pinfunction "2_2") (pintype "passive"))
    )
    (net (code "196") (name "V_ON_14V") (class "Default")
      (node (ref "5V") (pin "7") (pinfunction "ON/~{OFF}_7") (pintype "passive"))
      (node (ref "R1") (pin "2") (pinfunction "2_2") (pintype "passive"))
      (node (ref "R2") (pin "1") (pinfunction "1_1") (pintype "passive"))
    )
    (net (code "197") (name "unconnected-(-15V-RT-Pad7)") (class "Default")
      (node (ref "-15V") (pin "7") (pinfunction "RT_7") (pintype "passive"))
    )
    (net (code "198") (name "unconnected-(-15V-SS{slash}TRK-Pad11)") (class "Default")
      (node (ref "-15V") (pin "11") (pinfunction "SS/TRK_11") (pintype "passive"))
    )
    (net (code "199") (name "unconnected-(-15V-SYNC-Pad6)") (class "Default")
      (node (ref "-15V") (pin "6") (pinfunction "SYNC_6") (pintype "input"))
    )
    (net (code "200") (name "unconnected-(5V-NC-Pad5)") (class "Default")
      (node (ref "5V") (pin "5") (pinfunction "NC_5") (pintype "passive"))
    )
    (net (code "201") (name "unconnected-(J3-Pad2)") (class "Default")
      (node (ref "J3") (pin "2") (pinfunction "2_2") (pintype "passive"))
    )
    (net (code "202") (name "unconnected-(J3-Pad3)") (class "Default")
      (node (ref "J3") (pin "3") (pinfunction "3_3") (pintype "passive"))
    )
    (net (code "203") (name "unconnected-(J3-Pad4)") (class "Default")
      (node (ref "J3") (pin "4") (pinfunction "4_4") (pintype "passive"))
    )
    (net (code "204") (name "unconnected-(J3-Pad13)") (class "Default")
      (node (ref "J3") (pin "13") (pinfunction "13_13") (pintype "passive"))
    )
    (net (code "205") (name "unconnected-(J3-Pad16)") (class "Default")
      (node (ref "J3") (pin "16") (pinfunction "16_16") (pintype "passive"))
    )
    (net (code "206") (name "unconnected-(J3-Pad17)") (class "Default")
      (node (ref "J3") (pin "17") (pinfunction "17_17") (pintype "passive"))
    )
    (net (code "207") (name "unconnected-(J3-Pad18)") (class "Default")
      (node (ref "J3") (pin "18") (pinfunction "18_18") (pintype "passive"))
    )
    (net (code "208") (name "unconnected-(J3-Pad21)") (class "Default")
      (node (ref "J3") (pin "21") (pinfunction "21_21") (pintype "passive"))
    )
    (net (code "209") (name "unconnected-(J3-Pad22)") (class "Default")
      (node (ref "J3") (pin "22") (pinfunction "22_22") (pintype "passive"))
    )
    (net (code "210") (name "unconnected-(J3-Pad23)") (class "Default")
      (node (ref "J3") (pin "23") (pinfunction "23_23") (pintype "passive"))
    )
    (net (code "211") (name "unconnected-(J3-Pad24)") (class "Default")
      (node (ref "J3") (pin "24") (pinfunction "24_24") (pintype "passive"))
    )
    (net (code "212") (name "unconnected-(J3-Pad50)") (class "Default")
      (node (ref "J3") (pin "50") (pinfunction "50_50") (pintype "passive"))
    )
    (net (code "213") (name "unconnected-(J4-Pad2)") (class "Default")
      (node (ref "J4") (pin "2") (pinfunction "2_2") (pintype "passive"))
    )
    (net (code "214") (name "unconnected-(J4-Pad3)") (class "Default")
      (node (ref "J4") (pin "3") (pinfunction "3_3") (pintype "passive"))
    )
    (net (code "215") (name "unconnected-(J4-Pad4)") (class "Default")
      (node (ref "J4") (pin "4") (pinfunction "4_4") (pintype "passive"))
    )
    (net (code "216") (name "unconnected-(J4-Pad13)") (class "Default")
      (node (ref "J4") (pin "13") (pinfunction "13_13") (pintype "passive"))
    )
    (net (code "217") (name "unconnected-(J4-Pad16)") (class "Default")
      (node (ref "J4") (pin "16") (pinfunction "16_16") (pintype "passive"))
    )
    (net (code "218") (name "unconnected-(J4-Pad17)") (class "Default")
      (node (ref "J4") (pin "17") (pinfunction "17_17") (pintype "passive"))
    )
    (net (code "219") (name "unconnected-(J4-Pad18)") (class "Default")
      (node (ref "J4") (pin "18") (pinfunction "18_18") (pintype "passive"))
    )
    (net (code "220") (name "unconnected-(J4-Pad21)") (class "Default")
      (node (ref "J4") (pin "21") (pinfunction "21_21") (pintype "passive"))
    )
    (net (code "221") (name "unconnected-(J4-Pad22)") (class "Default")
      (node (ref "J4") (pin "22") (pinfunction "22_22") (pintype "passive"))
    )
    (net (code "222") (name "unconnected-(J4-Pad23)") (class "Default")
      (node (ref "J4") (pin "23") (pinfunction "23_23") (pintype "passive"))
    )
    (net (code "223") (name "unconnected-(J4-Pad24)") (class "Default")
      (node (ref "J4") (pin "24") (pinfunction "24_24") (pintype "passive"))
    )
    (net (code "224") (name "unconnected-(J4-Pad50)") (class "Default")
      (node (ref "J4") (pin "50") (pinfunction "50_50") (pintype "passive"))
    )
    (net (code "225") (name "unconnected-(LEVEL_SHIFTER1-A4-Pad5)") (class "Default")
      (node (ref "LEVEL_SHIFTER1") (pin "5") (pinfunction "A4_5") (pintype "bidirectional"))
    )
    (net (code "226") (name "unconnected-(LEVEL_SHIFTER1-B4-Pad10)") (class "Default")
      (node (ref "LEVEL_SHIFTER1") (pin "10") (pinfunction "B4_10") (pintype "bidirectional"))
    )
    (net (code "227") (name "unconnected-(LEVEL_SHIFTER1-NC-Pad9)") (class "Default")
      (node (ref "LEVEL_SHIFTER1") (pin "9") (pinfunction "NC_9") (pintype "no_connect"))
    )
    (net (code "228") (name "unconnected-(LEVEL_SHIFTER1-NC_2-Pad6)") (class "Default")
      (node (ref "LEVEL_SHIFTER1") (pin "6") (pinfunction "NC_2_6") (pintype "no_connect"))
    )
    (net (code "229") (name "unconnected-(LEVEL_SHIFTER2-NC-Pad9)") (class "Default")
      (node (ref "LEVEL_SHIFTER2") (pin "9") (pinfunction "NC_9") (pintype "no_connect"))
    )
    (net (code "230") (name "unconnected-(LEVEL_SHIFTER2-NC_2-Pad6)") (class "Default")
      (node (ref "LEVEL_SHIFTER2") (pin "6") (pinfunction "NC_2_6") (pintype "no_connect"))
    )
    (net (code "231") (name "unconnected-(LEVEL_SHIFTER3-NC-Pad9)") (class "Default")
      (node (ref "LEVEL_SHIFTER3") (pin "9") (pinfunction "NC_9") (pintype "no_connect"))
    )
    (net (code "232") (name "unconnected-(LEVEL_SHIFTER3-NC_2-Pad6)") (class "Default")
      (node (ref "LEVEL_SHIFTER3") (pin "6") (pinfunction "NC_2_6") (pintype "no_connect"))
    )
    (net (code "233") (name "unconnected-(LEVEL_SHIFTER4-A4-Pad5)") (class "Default")
      (node (ref "LEVEL_SHIFTER4") (pin "5") (pinfunction "A4_5") (pintype "bidirectional"))
    )
    (net (code "234") (name "unconnected-(LEVEL_SHIFTER4-B4-Pad10)") (class "Default")
      (node (ref "LEVEL_SHIFTER4") (pin "10") (pinfunction "B4_10") (pintype "bidirectional"))
    )
    (net (code "235") (name "unconnected-(LEVEL_SHIFTER4-NC-Pad9)") (class "Default")
      (node (ref "LEVEL_SHIFTER4") (pin "9") (pinfunction "NC_9") (pintype "no_connect"))
    )
    (net (code "236") (name "unconnected-(LEVEL_SHIFTER4-NC_2-Pad6)") (class "Default")
      (node (ref "LEVEL_SHIFTER4") (pin "6") (pinfunction "NC_2_6") (pintype "no_connect"))
    )
    (net (code "237") (name "unconnected-(LINE_DRIVER1-4A-Pad19)") (class "Default")
      (node (ref "LINE_DRIVER1") (pin "19") (pinfunction "4A_19") (pintype "input"))
    )
    (net (code "238") (name "unconnected-(LINE_DRIVER1-4Y-Pad18)") (class "Default")
      (node (ref "LINE_DRIVER1") (pin "18") (pinfunction "4Y_18") (pintype "output"))
    )
    (net (code "239") (name "unconnected-(LINE_DRIVER1-4Z-Pad16)") (class "Default")
      (node (ref "LINE_DRIVER1") (pin "16") (pinfunction "4Z_16") (pintype "output"))
    )
    (net (code "240") (name "unconnected-(LINE_DRIVER1-NC-Pad17)") (class "Default")
      (node (ref "LINE_DRIVER1") (pin "17") (pinfunction "NC_17") (pintype "passive"))
    )
    (net (code "241") (name "unconnected-(LINE_DRIVER1-NC_2-Pad3)") (class "Default")
      (node (ref "LINE_DRIVER1") (pin "3") (pinfunction "NC_2_3") (pintype "passive"))
    )
    (net (code "242") (name "unconnected-(LINE_DRIVER1-NC_3-Pad7)") (class "Default")
      (node (ref "LINE_DRIVER1") (pin "7") (pinfunction "NC_3_7") (pintype "passive"))
    )
    (net (code "243") (name "unconnected-(LINE_DRIVER1-NC_4-Pad13)") (class "Default")
      (node (ref "LINE_DRIVER1") (pin "13") (pinfunction "NC_4_13") (pintype "passive"))
    )
    (net (code "244") (name "unconnected-(LINE_DRIVER2-4A-Pad19)") (class "Default")
      (node (ref "LINE_DRIVER2") (pin "19") (pinfunction "4A_19") (pintype "input"))
    )
    (net (code "245") (name "unconnected-(LINE_DRIVER2-4Y-Pad18)") (class "Default")
      (node (ref "LINE_DRIVER2") (pin "18") (pinfunction "4Y_18") (pintype "output"))
    )
    (net (code "246") (name "unconnected-(LINE_DRIVER2-4Z-Pad16)") (class "Default")
      (node (ref "LINE_DRIVER2") (pin "16") (pinfunction "4Z_16") (pintype "output"))
    )
    (net (code "247") (name "unconnected-(LINE_DRIVER2-NC-Pad17)") (class "Default")
      (node (ref "LINE_DRIVER2") (pin "17") (pinfunction "NC_17") (pintype "passive"))
    )
    (net (code "248") (name "unconnected-(LINE_DRIVER2-NC_2-Pad3)") (class "Default")
      (node (ref "LINE_DRIVER2") (pin "3") (pinfunction "NC_2_3") (pintype "passive"))
    )
    (net (code "249") (name "unconnected-(LINE_DRIVER2-NC_3-Pad7)") (class "Default")
      (node (ref "LINE_DRIVER2") (pin "7") (pinfunction "NC_3_7") (pintype "passive"))
    )
    (net (code "250") (name "unconnected-(LINE_DRIVER2-NC_4-Pad13)") (class "Default")
      (node (ref "LINE_DRIVER2") (pin "13") (pinfunction "NC_4_13") (pintype "passive"))
    )
    (net (code "251") (name "unconnected-(LINE_RECEIVER2-4A-Pad14)") (class "Default")
      (node (ref "LINE_RECEIVER2") (pin "14") (pinfunction "4A_14") (pintype "input"))
    )
    (net (code "252") (name "unconnected-(LINE_RECEIVER2-4B-Pad15)") (class "Default")
      (node (ref "LINE_RECEIVER2") (pin "15") (pinfunction "4B_15") (pintype "input"))
    )
    (net (code "253") (name "unconnected-(LINE_RECEIVER2-4Y-Pad13)") (class "Default")
      (node (ref "LINE_RECEIVER2") (pin "13") (pinfunction "4Y_13") (pintype "output"))
    )
    (net (code "254") (name "unconnected-(LINE_RECEIVER4-4A-Pad14)") (class "Default")
      (node (ref "LINE_RECEIVER4") (pin "14") (pinfunction "4A_14") (pintype "input"))
    )
    (net (code "255") (name "unconnected-(LINE_RECEIVER4-4B-Pad15)") (class "Default")
      (node (ref "LINE_RECEIVER4") (pin "15") (pinfunction "4B_15") (pintype "input"))
    )
    (net (code "256") (name "unconnected-(LINE_RECEIVER4-4Y-Pad13)") (class "Default")
      (node (ref "LINE_RECEIVER4") (pin "13") (pinfunction "4Y_13") (pintype "output"))
    )
    (net (code "257") (name "unconnected-(OPTOCOUPLER2-ANODE4-Pad7)") (class "Default")
      (node (ref "OPTOCOUPLER2") (pin "7") (pinfunction "ANODE4_7") (pintype "bidirectional"))
    )
    (net (code "258") (name "unconnected-(OPTOCOUPLER2-CATHODE4-Pad8)") (class "Default")
      (node (ref "OPTOCOUPLER2") (pin "8") (pinfunction "CATHODE4_8") (pintype "bidirectional"))
    )
    (net (code "259") (name "unconnected-(OPTOCOUPLER2-V04-Pad11)") (class "Default")
      (node (ref "OPTOCOUPLER2") (pin "11") (pinfunction "V04_11") (pintype "bidirectional"))
    )
    (net (code "260") (name "unconnected-(OP_AMP-+IN_3-Pad10)") (class "Default")
      (node (ref "OP_AMP") (pin "10") (pinfunction "+IN_3_10") (pintype "output"))
    )
    (net (code "261") (name "unconnected-(OP_AMP--IN_3-Pad9)") (class "Default")
      (node (ref "OP_AMP") (pin "9") (pinfunction "-IN_3_9") (pintype "output"))
    )
    (net (code "262") (name "unconnected-(OP_AMP-OUT_3-Pad8)") (class "Default")
      (node (ref "OP_AMP") (pin "8") (pinfunction "OUT_3_8") (pintype "output"))
    )
    (net (code "263") (name "unconnected-(ST-LINK_CONNECTOR-Pad5)") (class "Default")
      (node (ref "ST-LINK_CONNECTOR") (pin "5") (pinfunction "5_5") (pintype "passive"))
    )
    (net (code "264") (name "unconnected-(ST-LINK_CONNECTOR-Pad7)") (class "Default")
      (node (ref "ST-LINK_CONNECTOR") (pin "7") (pinfunction "7_7") (pintype "passive"))
    )
    (net (code "265") (name "unconnected-(ST-LINK_CONNECTOR-Pad8)") (class "Default")
      (node (ref "ST-LINK_CONNECTOR") (pin "8") (pinfunction "8_8") (pintype "passive"))
    )
    (net (code "266") (name "unconnected-(ST-LINK_CONNECTOR-Pad9)") (class "Default")
      (node (ref "ST-LINK_CONNECTOR") (pin "9") (pinfunction "9_9") (pintype "passive"))
    )
    (net (code "267") (name "unconnected-(ST-LINK_CONNECTOR-Pad10)") (class "Default")
      (node (ref "ST-LINK_CONNECTOR") (pin "10") (pinfunction "10_10") (pintype "passive"))
    )
    (net (code "268") (name "unconnected-(STM32F2A-PA0-WKUP-Pad23)") (class "Default")
      (node (ref "STM32F2") (pin "23") (pinfunction "PA0-WKUP_23") (pintype "bidirectional"))
    )
    (net (code "269") (name "unconnected-(STM32F2A-PA1-Pad24)") (class "Default")
      (node (ref "STM32F2") (pin "24") (pinfunction "PA1_24") (pintype "bidirectional"))
    )
    (net (code "270") (name "unconnected-(STM32F2A-PA3-Pad26)") (class "Default")
      (node (ref "STM32F2") (pin "26") (pinfunction "PA3_26") (pintype "bidirectional"))
    )
    (net (code "271") (name "unconnected-(STM32F2A-PC0-Pad15)") (class "Default")
      (node (ref "STM32F2") (pin "15") (pinfunction "PC0_15") (pintype "bidirectional"))
    )
    (net (code "272") (name "unconnected-(STM32F2A-PC1-Pad16)") (class "Default")
      (node (ref "STM32F2") (pin "16") (pinfunction "PC1_16") (pintype "bidirectional"))
    )
    (net (code "273") (name "unconnected-(STM32F2A-PC2-Pad17)") (class "Default")
      (node (ref "STM32F2") (pin "17") (pinfunction "PC2_17") (pintype "bidirectional"))
    )
    (net (code "274") (name "unconnected-(STM32F2A-PC3-Pad18)") (class "Default")
      (node (ref "STM32F2") (pin "18") (pinfunction "PC3_18") (pintype "bidirectional"))
    )
    (net (code "275") (name "unconnected-(STM32F2A-PC13-Pad7)") (class "Default")
      (node (ref "STM32F2") (pin "7") (pinfunction "PC13_7") (pintype "bidirectional"))
    )
    (net (code "276") (name "unconnected-(STM32F2A-PC14{slash}OSC32_IN-Pad8)") (class "Default")
      (node (ref "STM32F2") (pin "8") (pinfunction "PC14/OSC32_IN_8") (pintype "bidirectional"))
    )
    (net (code "277") (name "unconnected-(STM32F2A-PC15-OSC32_OUT-Pad9)") (class "Default")
      (node (ref "STM32F2") (pin "9") (pinfunction "PC15-OSC32_OUT_9") (pintype "bidirectional"))
    )
    (net (code "278") (name "unconnected-(STM32F2A-PD6-Pad87)") (class "Default")
      (node (ref "STM32F2") (pin "87") (pinfunction "PD6_87") (pintype "bidirectional"))
    )
    (net (code "279") (name "unconnected-(STM32F2A-PD7-Pad88)") (class "Default")
      (node (ref "STM32F2") (pin "88") (pinfunction "PD7_88") (pintype "bidirectional"))
    )
    (net (code "280") (name "unconnected-(STM32F2B-PE6-Pad5)") (class "Default")
      (node (ref "STM32F2") (pin "5") (pinfunction "PE6_5") (pintype "bidirectional"))
    )
    (net (code "281") (name "unconnected-(STM32F2B-PE10-Pad41)") (class "Default")
      (node (ref "STM32F2") (pin "41") (pinfunction "PE10_41") (pintype "bidirectional"))
    )
    (net (code "282") (name "unconnected-(STM32F2B-PE12-Pad43)") (class "Default")
      (node (ref "STM32F2") (pin "43") (pinfunction "PE12_43") (pintype "bidirectional"))
    )
    (net (code "283") (name "unconnected-(STM32F2B-PH1{slash}OSC_OUT-Pad13)") (class "Default")
      (node (ref "STM32F2") (pin "13") (pinfunction "PH1/OSC_OUT_13") (pintype "bidirectional"))
    )
    (net (code "284") (name "unconnected-(STM32F2B-RFU-Pad99)") (class "Default")
      (node (ref "STM32F2") (pin "99") (pinfunction "RFU_99") (pintype "passive"))
    )
    (net (code "285") (name "unconnected-(UART_CONNECTOR-Pad03)") (class "Default")
      (node (ref "UART_CONNECTOR") (pin "03") (pinfunction "03_03") (pintype "passive"))
    )
    (net (code "286") (name "unconnected-(UART_CONNECTOR-Pad06)") (class "Default")
      (node (ref "UART_CONNECTOR") (pin "06") (pinfunction "06_06") (pintype "passive"))
    )
  )
)
